# ledCubeV2_0.net
KiCad netlist of a schematic drawn in EAGLE
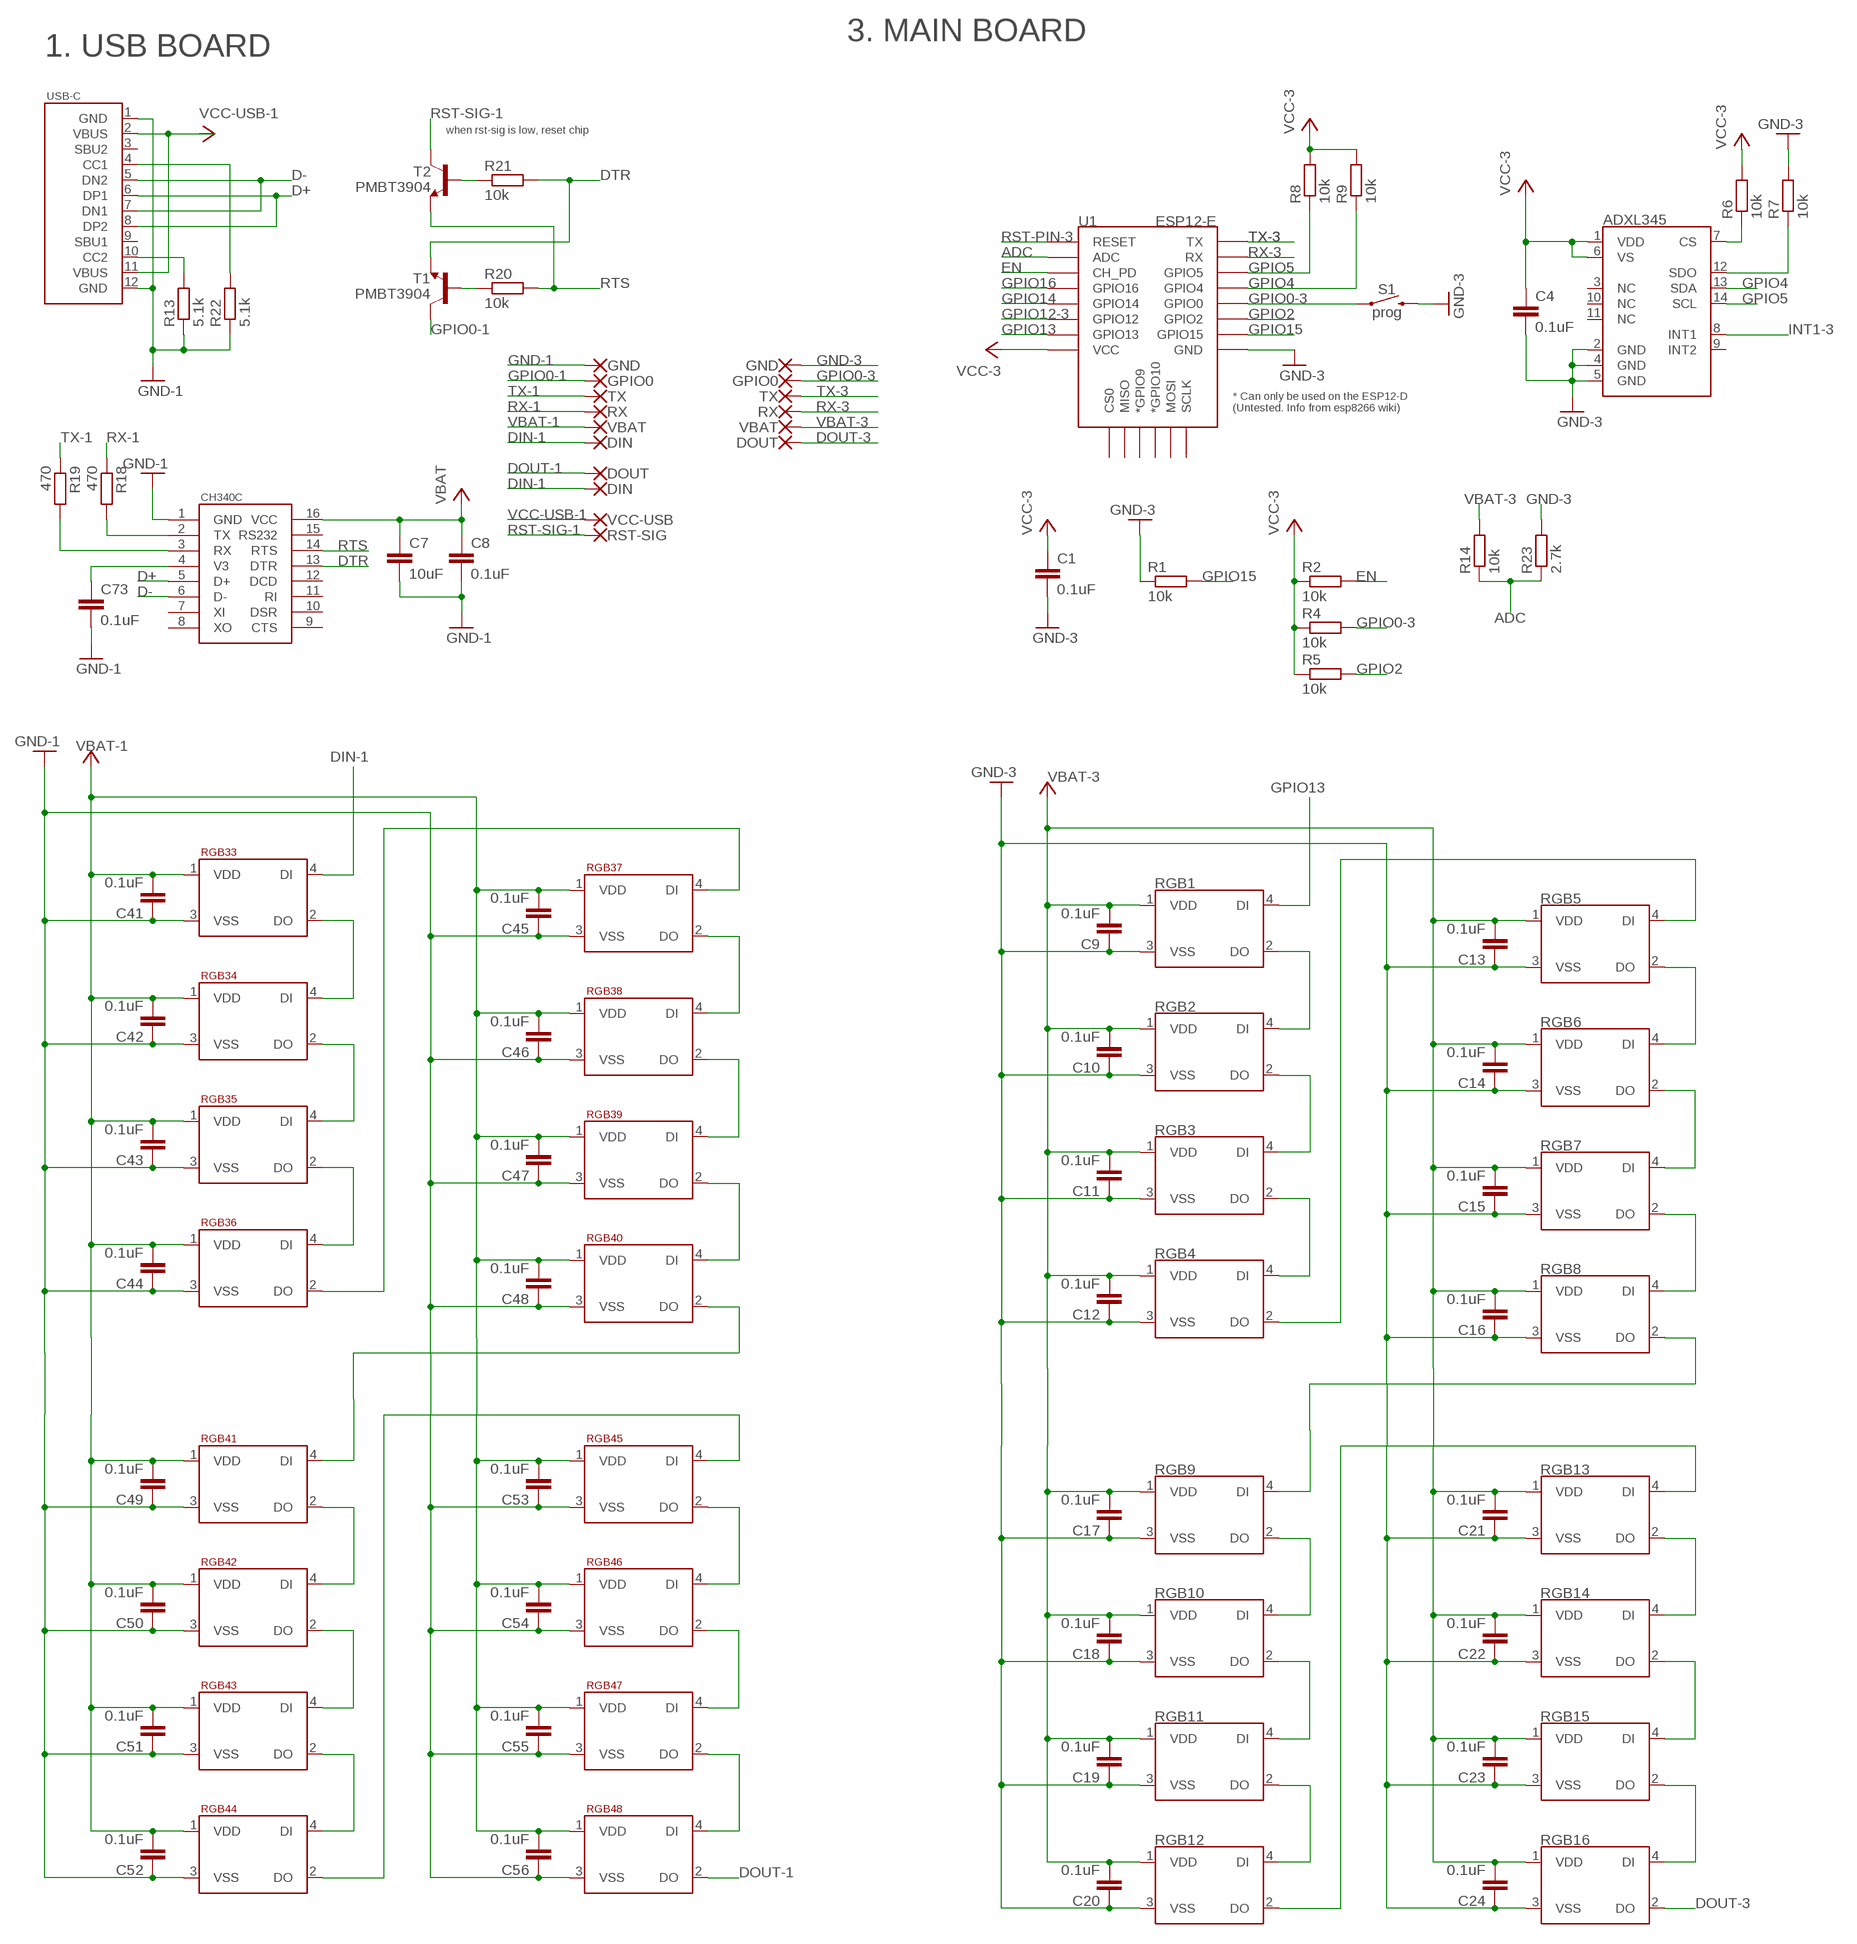
[diagram p0: schematic, sheet 1, part 1 of 2]
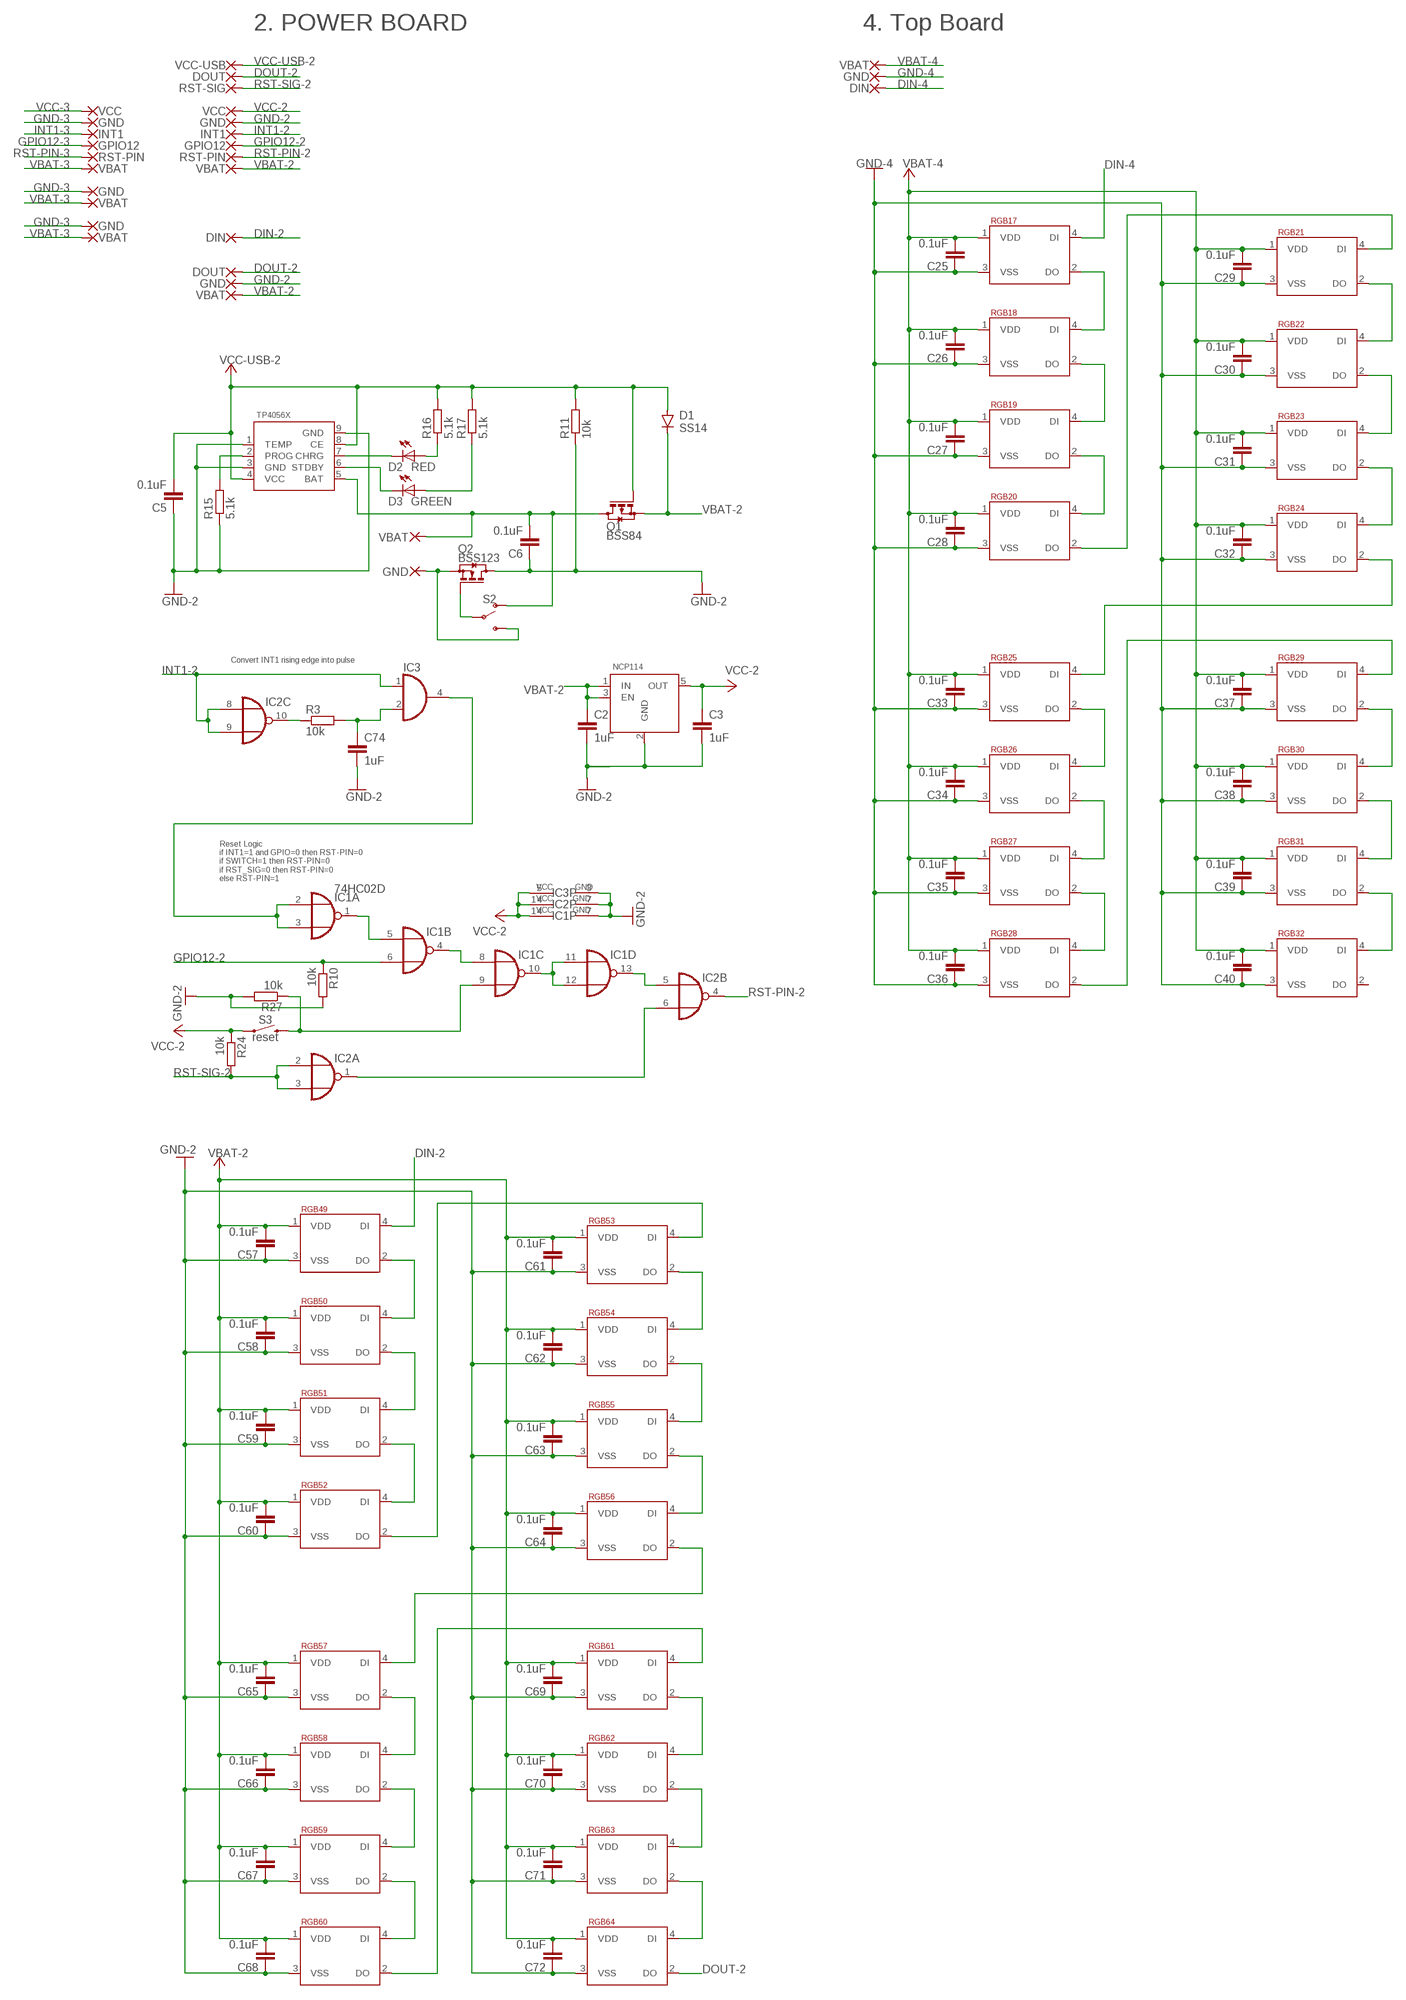
[diagram p1: schematic, sheet 1, part 2 of 2]

(export (version "E")
  (design (tool "Eeschema 10.0.6"))
  (components
    (comp (ref "ADXL345")
      (value "ADXL345")
      (footprint "eagle-import:LGA-14")
      (libsource (lib "eagle-import") (part "ADXL345"))
    )
    (comp (ref "C1")
      (value "0.1uF")
      (footprint "eagle-import:C0603")
      (libsource (lib "eagle-import") (part "CC0603"))
    )
    (comp (ref "C2")
      (value "1uF")
      (footprint "eagle-import:C0603")
      (libsource (lib "eagle-import") (part "CC0603"))
    )
    (comp (ref "C3")
      (value "1uF")
      (footprint "eagle-import:C0603")
      (libsource (lib "eagle-import") (part "CC0603"))
    )
    (comp (ref "C4")
      (value "0.1uF")
      (footprint "eagle-import:C0603")
      (libsource (lib "eagle-import") (part "CC0603"))
    )
    (comp (ref "C5")
      (value "0.1uF")
      (footprint "eagle-import:C0603")
      (libsource (lib "eagle-import") (part "CC0603"))
    )
    (comp (ref "C6")
      (value "0.1uF")
      (footprint "eagle-import:C0603")
      (libsource (lib "eagle-import") (part "CC0603"))
    )
    (comp (ref "C7")
      (value "10uF")
      (footprint "eagle-import:C0603")
      (libsource (lib "eagle-import") (part "CC0603"))
    )
    (comp (ref "C8")
      (value "0.1uF")
      (footprint "eagle-import:C0603")
      (libsource (lib "eagle-import") (part "CC0603"))
    )
    (comp (ref "C9")
      (value "0.1uF")
      (footprint "eagle-import:C0603")
      (libsource (lib "eagle-import") (part "CC0603"))
    )
    (comp (ref "C10")
      (value "0.1uF")
      (footprint "eagle-import:C0603")
      (libsource (lib "eagle-import") (part "CC0603"))
    )
    (comp (ref "C11")
      (value "0.1uF")
      (footprint "eagle-import:C0603")
      (libsource (lib "eagle-import") (part "CC0603"))
    )
    (comp (ref "C12")
      (value "0.1uF")
      (footprint "eagle-import:C0603")
      (libsource (lib "eagle-import") (part "CC0603"))
    )
    (comp (ref "C13")
      (value "0.1uF")
      (footprint "eagle-import:C0603")
      (libsource (lib "eagle-import") (part "CC0603"))
    )
    (comp (ref "C14")
      (value "0.1uF")
      (footprint "eagle-import:C0603")
      (libsource (lib "eagle-import") (part "CC0603"))
    )
    (comp (ref "C15")
      (value "0.1uF")
      (footprint "eagle-import:C0603")
      (libsource (lib "eagle-import") (part "CC0603"))
    )
    (comp (ref "C16")
      (value "0.1uF")
      (footprint "eagle-import:C0603")
      (libsource (lib "eagle-import") (part "CC0603"))
    )
    (comp (ref "C17")
      (value "0.1uF")
      (footprint "eagle-import:C0603")
      (libsource (lib "eagle-import") (part "CC0603"))
    )
    (comp (ref "C18")
      (value "0.1uF")
      (footprint "eagle-import:C0603")
      (libsource (lib "eagle-import") (part "CC0603"))
    )
    (comp (ref "C19")
      (value "0.1uF")
      (footprint "eagle-import:C0603")
      (libsource (lib "eagle-import") (part "CC0603"))
    )
    (comp (ref "C20")
      (value "0.1uF")
      (footprint "eagle-import:C0603")
      (libsource (lib "eagle-import") (part "CC0603"))
    )
    (comp (ref "C21")
      (value "0.1uF")
      (footprint "eagle-import:C0603")
      (libsource (lib "eagle-import") (part "CC0603"))
    )
    (comp (ref "C22")
      (value "0.1uF")
      (footprint "eagle-import:C0603")
      (libsource (lib "eagle-import") (part "CC0603"))
    )
    (comp (ref "C23")
      (value "0.1uF")
      (footprint "eagle-import:C0603")
      (libsource (lib "eagle-import") (part "CC0603"))
    )
    (comp (ref "C24")
      (value "0.1uF")
      (footprint "eagle-import:C0603")
      (libsource (lib "eagle-import") (part "CC0603"))
    )
    (comp (ref "C25")
      (value "0.1uF")
      (footprint "eagle-import:C0603")
      (libsource (lib "eagle-import") (part "CC0603"))
    )
    (comp (ref "C26")
      (value "0.1uF")
      (footprint "eagle-import:C0603")
      (libsource (lib "eagle-import") (part "CC0603"))
    )
    (comp (ref "C27")
      (value "0.1uF")
      (footprint "eagle-import:C0603")
      (libsource (lib "eagle-import") (part "CC0603"))
    )
    (comp (ref "C28")
      (value "0.1uF")
      (footprint "eagle-import:C0603")
      (libsource (lib "eagle-import") (part "CC0603"))
    )
    (comp (ref "C29")
      (value "0.1uF")
      (footprint "eagle-import:C0603")
      (libsource (lib "eagle-import") (part "CC0603"))
    )
    (comp (ref "C30")
      (value "0.1uF")
      (footprint "eagle-import:C0603")
      (libsource (lib "eagle-import") (part "CC0603"))
    )
    (comp (ref "C31")
      (value "0.1uF")
      (footprint "eagle-import:C0603")
      (libsource (lib "eagle-import") (part "CC0603"))
    )
    (comp (ref "C32")
      (value "0.1uF")
      (footprint "eagle-import:C0603")
      (libsource (lib "eagle-import") (part "CC0603"))
    )
    (comp (ref "C33")
      (value "0.1uF")
      (footprint "eagle-import:C0603")
      (libsource (lib "eagle-import") (part "CC0603"))
    )
    (comp (ref "C34")
      (value "0.1uF")
      (footprint "eagle-import:C0603")
      (libsource (lib "eagle-import") (part "CC0603"))
    )
    (comp (ref "C35")
      (value "0.1uF")
      (footprint "eagle-import:C0603")
      (libsource (lib "eagle-import") (part "CC0603"))
    )
    (comp (ref "C36")
      (value "0.1uF")
      (footprint "eagle-import:C0603")
      (libsource (lib "eagle-import") (part "CC0603"))
    )
    (comp (ref "C37")
      (value "0.1uF")
      (footprint "eagle-import:C0603")
      (libsource (lib "eagle-import") (part "CC0603"))
    )
    (comp (ref "C38")
      (value "0.1uF")
      (footprint "eagle-import:C0603")
      (libsource (lib "eagle-import") (part "CC0603"))
    )
    (comp (ref "C39")
      (value "0.1uF")
      (footprint "eagle-import:C0603")
      (libsource (lib "eagle-import") (part "CC0603"))
    )
    (comp (ref "C40")
      (value "0.1uF")
      (footprint "eagle-import:C0603")
      (libsource (lib "eagle-import") (part "CC0603"))
    )
    (comp (ref "C41")
      (value "0.1uF")
      (footprint "eagle-import:C0603")
      (libsource (lib "eagle-import") (part "CC0603"))
    )
    (comp (ref "C42")
      (value "0.1uF")
      (footprint "eagle-import:C0603")
      (libsource (lib "eagle-import") (part "CC0603"))
    )
    (comp (ref "C43")
      (value "0.1uF")
      (footprint "eagle-import:C0603")
      (libsource (lib "eagle-import") (part "CC0603"))
    )
    (comp (ref "C44")
      (value "0.1uF")
      (footprint "eagle-import:C0603")
      (libsource (lib "eagle-import") (part "CC0603"))
    )
    (comp (ref "C45")
      (value "0.1uF")
      (footprint "eagle-import:C0603")
      (libsource (lib "eagle-import") (part "CC0603"))
    )
    (comp (ref "C46")
      (value "0.1uF")
      (footprint "eagle-import:C0603")
      (libsource (lib "eagle-import") (part "CC0603"))
    )
    (comp (ref "C47")
      (value "0.1uF")
      (footprint "eagle-import:C0603")
      (libsource (lib "eagle-import") (part "CC0603"))
    )
    (comp (ref "C48")
      (value "0.1uF")
      (footprint "eagle-import:C0603")
      (libsource (lib "eagle-import") (part "CC0603"))
    )
    (comp (ref "C49")
      (value "0.1uF")
      (footprint "eagle-import:C0603")
      (libsource (lib "eagle-import") (part "CC0603"))
    )
    (comp (ref "C50")
      (value "0.1uF")
      (footprint "eagle-import:C0603")
      (libsource (lib "eagle-import") (part "CC0603"))
    )
    (comp (ref "C51")
      (value "0.1uF")
      (footprint "eagle-import:C0603")
      (libsource (lib "eagle-import") (part "CC0603"))
    )
    (comp (ref "C52")
      (value "0.1uF")
      (footprint "eagle-import:C0603")
      (libsource (lib "eagle-import") (part "CC0603"))
    )
    (comp (ref "C53")
      (value "0.1uF")
      (footprint "eagle-import:C0603")
      (libsource (lib "eagle-import") (part "CC0603"))
    )
    (comp (ref "C54")
      (value "0.1uF")
      (footprint "eagle-import:C0603")
      (libsource (lib "eagle-import") (part "CC0603"))
    )
    (comp (ref "C55")
      (value "0.1uF")
      (footprint "eagle-import:C0603")
      (libsource (lib "eagle-import") (part "CC0603"))
    )
    (comp (ref "C56")
      (value "0.1uF")
      (footprint "eagle-import:C0603")
      (libsource (lib "eagle-import") (part "CC0603"))
    )
    (comp (ref "C57")
      (value "0.1uF")
      (footprint "eagle-import:C0603")
      (libsource (lib "eagle-import") (part "CC0603"))
    )
    (comp (ref "C58")
      (value "0.1uF")
      (footprint "eagle-import:C0603")
      (libsource (lib "eagle-import") (part "CC0603"))
    )
    (comp (ref "C59")
      (value "0.1uF")
      (footprint "eagle-import:C0603")
      (libsource (lib "eagle-import") (part "CC0603"))
    )
    (comp (ref "C60")
      (value "0.1uF")
      (footprint "eagle-import:C0603")
      (libsource (lib "eagle-import") (part "CC0603"))
    )
    (comp (ref "C61")
      (value "0.1uF")
      (footprint "eagle-import:C0603")
      (libsource (lib "eagle-import") (part "CC0603"))
    )
    (comp (ref "C62")
      (value "0.1uF")
      (footprint "eagle-import:C0603")
      (libsource (lib "eagle-import") (part "CC0603"))
    )
    (comp (ref "C63")
      (value "0.1uF")
      (footprint "eagle-import:C0603")
      (libsource (lib "eagle-import") (part "CC0603"))
    )
    (comp (ref "C64")
      (value "0.1uF")
      (footprint "eagle-import:C0603")
      (libsource (lib "eagle-import") (part "CC0603"))
    )
    (comp (ref "C65")
      (value "0.1uF")
      (footprint "eagle-import:C0603")
      (libsource (lib "eagle-import") (part "CC0603"))
    )
    (comp (ref "C66")
      (value "0.1uF")
      (footprint "eagle-import:C0603")
      (libsource (lib "eagle-import") (part "CC0603"))
    )
    (comp (ref "C67")
      (value "0.1uF")
      (footprint "eagle-import:C0603")
      (libsource (lib "eagle-import") (part "CC0603"))
    )
    (comp (ref "C68")
      (value "0.1uF")
      (footprint "eagle-import:C0603")
      (libsource (lib "eagle-import") (part "CC0603"))
    )
    (comp (ref "C69")
      (value "0.1uF")
      (footprint "eagle-import:C0603")
      (libsource (lib "eagle-import") (part "CC0603"))
    )
    (comp (ref "C70")
      (value "0.1uF")
      (footprint "eagle-import:C0603")
      (libsource (lib "eagle-import") (part "CC0603"))
    )
    (comp (ref "C71")
      (value "0.1uF")
      (footprint "eagle-import:C0603")
      (libsource (lib "eagle-import") (part "CC0603"))
    )
    (comp (ref "C72")
      (value "0.1uF")
      (footprint "eagle-import:C0603")
      (libsource (lib "eagle-import") (part "CC0603"))
    )
    (comp (ref "C73")
      (value "0.1uF")
      (footprint "eagle-import:C0603")
      (libsource (lib "eagle-import") (part "CC0603"))
    )
    (comp (ref "C74")
      (value "1uF")
      (footprint "eagle-import:C0603")
      (libsource (lib "eagle-import") (part "CC0603"))
    )
    (comp (ref "CH340C")
      (value "CH340G")
      (footprint "eagle-import:SOIC16")
      (libsource (lib "eagle-import") (part "CH340G"))
    )
    (comp (ref "D1")
      (value "SS14")
      (footprint "eagle-import:DO-214AC")
      (libsource (lib "eagle-import") (part "DIODE-DO-214AC"))
    )
    (comp (ref "D2")
      (value "RED")
      (footprint "eagle-import:LED_SML0603")
      (libsource (lib "eagle-import") (part "LED_ESML0603"))
    )
    (comp (ref "D3")
      (value "GREEN")
      (footprint "eagle-import:LED_SML0603")
      (libsource (lib "eagle-import") (part "LED_ESML0603"))
    )
    (comp (ref "GND")
      (value "SMD2")
      (footprint "eagle-import:SMD1,27-2,54")
      (libsource (lib "eagle-import") (part "SMD2"))
    )
    (comp (ref "GND-1")
      (value "GND")
      (footprint "eagle-import:SMD1,27-2,54")
      (libsource (lib "eagle-import") (part "SMD2"))
    )
    (comp (ref "GND-2")
      (value "RX")
      (footprint "eagle-import:SMD1,27-2,54")
      (libsource (lib "eagle-import") (part "SMD2"))
    )
    (comp (ref "GPIO0-1")
      (value "GPIO0")
      (footprint "eagle-import:SMD1,27-2,54")
      (libsource (lib "eagle-import") (part "SMD2"))
    )
    (comp (ref "GPIO0-2")
      (value "GPIO0")
      (footprint "eagle-import:SMD1,27-2,54")
      (libsource (lib "eagle-import") (part "SMD2"))
    )
    (comp (ref "IC1")
      (value "74HC02D")
      (footprint "eagle-import:SO14")
      (libsource (lib "eagle-import") (part "7402DHC"))
    )
    (comp (ref "IC2")
      (value "74HC02D")
      (footprint "eagle-import:SO14")
      (libsource (lib "eagle-import") (part "7402DHC"))
    )
    (comp (ref "IC3")
      (value "74AHC1G08DCK")
      (footprint "eagle-import:SC70-5")
      (libsource (lib "eagle-import") (part "741G08DCKAHC"))
    )
    (comp (ref "NCP114")
      (value "NCP114")
      (footprint "eagle-import:TSOP-5")
      (libsource (lib "eagle-import") (part "NCP114"))
    )
    (comp (ref "Q1")
      (value "BSS84")
      (footprint "eagle-import:SOT23")
      (libsource (lib "eagle-import") (part "BSS84"))
    )
    (comp (ref "Q2")
      (value "BSS123")
      (footprint "eagle-import:SOT23")
      (libsource (lib "eagle-import") (part "BSS123"))
    )
    (comp (ref "R1")
      (value "10k")
      (footprint "eagle-import:R0603")
      (libsource (lib "eagle-import") (part "RR0603"))
    )
    (comp (ref "R2")
      (value "10k")
      (footprint "eagle-import:R0603")
      (libsource (lib "eagle-import") (part "RR0603"))
    )
    (comp (ref "R3")
      (value "10k")
      (footprint "eagle-import:R0603")
      (libsource (lib "eagle-import") (part "RR0603"))
    )
    (comp (ref "R4")
      (value "10k")
      (footprint "eagle-import:R0603")
      (libsource (lib "eagle-import") (part "RR0603"))
    )
    (comp (ref "R5")
      (value "10k")
      (footprint "eagle-import:R0603")
      (libsource (lib "eagle-import") (part "RR0603"))
    )
    (comp (ref "R6")
      (value "10k")
      (footprint "eagle-import:R0603")
      (libsource (lib "eagle-import") (part "RR0603"))
    )
    (comp (ref "R7")
      (value "10k")
      (footprint "eagle-import:R0603")
      (libsource (lib "eagle-import") (part "RR0603"))
    )
    (comp (ref "R8")
      (value "10k")
      (footprint "eagle-import:R0603")
      (libsource (lib "eagle-import") (part "RR0603"))
    )
    (comp (ref "R9")
      (value "10k")
      (footprint "eagle-import:R0603")
      (libsource (lib "eagle-import") (part "RR0603"))
    )
    (comp (ref "R10")
      (value "10k")
      (footprint "eagle-import:R0603")
      (libsource (lib "eagle-import") (part "RR0603"))
    )
    (comp (ref "R11")
      (value "10k")
      (footprint "eagle-import:R0603")
      (libsource (lib "eagle-import") (part "RR0603"))
    )
    (comp (ref "R13")
      (value "5.1k")
      (footprint "eagle-import:R0603")
      (libsource (lib "eagle-import") (part "RR0603"))
    )
    (comp (ref "R14")
      (value "10k")
      (footprint "eagle-import:R0603")
      (libsource (lib "eagle-import") (part "RR0603"))
    )
    (comp (ref "R15")
      (value "5.1k")
      (footprint "eagle-import:R0603")
      (libsource (lib "eagle-import") (part "RR0603"))
    )
    (comp (ref "R16")
      (value "5.1k")
      (footprint "eagle-import:R0603")
      (libsource (lib "eagle-import") (part "RR0603"))
    )
    (comp (ref "R17")
      (value "5.1k")
      (footprint "eagle-import:R0603")
      (libsource (lib "eagle-import") (part "RR0603"))
    )
    (comp (ref "R18")
      (value "470")
      (footprint "eagle-import:R0603")
      (libsource (lib "eagle-import") (part "RR0603"))
    )
    (comp (ref "R19")
      (value "470")
      (footprint "eagle-import:R0603")
      (libsource (lib "eagle-import") (part "RR0603"))
    )
    (comp (ref "R20")
      (value "10k")
      (footprint "eagle-import:R0603")
      (libsource (lib "eagle-import") (part "RR0603"))
    )
    (comp (ref "R21")
      (value "10k")
      (footprint "eagle-import:R0603")
      (libsource (lib "eagle-import") (part "RR0603"))
    )
    (comp (ref "R22")
      (value "5.1k")
      (footprint "eagle-import:R0603")
      (libsource (lib "eagle-import") (part "RR0603"))
    )
    (comp (ref "R23")
      (value "2.7k")
      (footprint "eagle-import:R0603")
      (libsource (lib "eagle-import") (part "RR0603"))
    )
    (comp (ref "R24")
      (value "10k")
      (footprint "eagle-import:R0603")
      (libsource (lib "eagle-import") (part "RR0603"))
    )
    (comp (ref "R27")
      (value "10k")
      (footprint "eagle-import:R0603")
      (libsource (lib "eagle-import") (part "RR0603"))
    )
    (comp (ref "RGB1")
      (value "WS2812B")
      (footprint "eagle-import:WS2812B-MINI")
      (libsource (lib "eagle-import") (part "WS2812B-MINI"))
    )
    (comp (ref "RGB2")
      (value "WS2812B")
      (footprint "eagle-import:WS2812B-MINI")
      (libsource (lib "eagle-import") (part "WS2812B-MINI"))
    )
    (comp (ref "RGB3")
      (value "WS2812B")
      (footprint "eagle-import:WS2812B-MINI")
      (libsource (lib "eagle-import") (part "WS2812B-MINI"))
    )
    (comp (ref "RGB4")
      (value "WS2812B")
      (footprint "eagle-import:WS2812B-MINI")
      (libsource (lib "eagle-import") (part "WS2812B-MINI"))
    )
    (comp (ref "RGB5")
      (value "WS2812B")
      (footprint "eagle-import:WS2812B-MINI")
      (libsource (lib "eagle-import") (part "WS2812B-MINI"))
    )
    (comp (ref "RGB6")
      (value "WS2812B")
      (footprint "eagle-import:WS2812B-MINI")
      (libsource (lib "eagle-import") (part "WS2812B-MINI"))
    )
    (comp (ref "RGB7")
      (value "WS2812B")
      (footprint "eagle-import:WS2812B-MINI")
      (libsource (lib "eagle-import") (part "WS2812B-MINI"))
    )
    (comp (ref "RGB8")
      (value "WS2812B")
      (footprint "eagle-import:WS2812B-MINI")
      (libsource (lib "eagle-import") (part "WS2812B-MINI"))
    )
    (comp (ref "RGB9")
      (value "WS2812B")
      (footprint "eagle-import:WS2812B-MINI")
      (libsource (lib "eagle-import") (part "WS2812B-MINI"))
    )
    (comp (ref "RGB10")
      (value "WS2812B")
      (footprint "eagle-import:WS2812B-MINI")
      (libsource (lib "eagle-import") (part "WS2812B-MINI"))
    )
    (comp (ref "RGB11")
      (value "WS2812B")
      (footprint "eagle-import:WS2812B-MINI")
      (libsource (lib "eagle-import") (part "WS2812B-MINI"))
    )
    (comp (ref "RGB12")
      (value "WS2812B")
      (footprint "eagle-import:WS2812B-MINI")
      (libsource (lib "eagle-import") (part "WS2812B-MINI"))
    )
    (comp (ref "RGB13")
      (value "WS2812B")
      (footprint "eagle-import:WS2812B-MINI")
      (libsource (lib "eagle-import") (part "WS2812B-MINI"))
    )
    (comp (ref "RGB14")
      (value "WS2812B")
      (footprint "eagle-import:WS2812B-MINI")
      (libsource (lib "eagle-import") (part "WS2812B-MINI"))
    )
    (comp (ref "RGB15")
      (value "WS2812B")
      (footprint "eagle-import:WS2812B-MINI")
      (libsource (lib "eagle-import") (part "WS2812B-MINI"))
    )
    (comp (ref "RGB16")
      (value "WS2812B")
      (footprint "eagle-import:WS2812B-MINI")
      (libsource (lib "eagle-import") (part "WS2812B-MINI"))
    )
    (comp (ref "RGB17")
      (value "WS2812B")
      (footprint "eagle-import:WS2812B-MINI")
      (libsource (lib "eagle-import") (part "WS2812B-MINI"))
    )
    (comp (ref "RGB18")
      (value "WS2812B")
      (footprint "eagle-import:WS2812B-MINI")
      (libsource (lib "eagle-import") (part "WS2812B-MINI"))
    )
    (comp (ref "RGB19")
      (value "WS2812B")
      (footprint "eagle-import:WS2812B-MINI")
      (libsource (lib "eagle-import") (part "WS2812B-MINI"))
    )
    (comp (ref "RGB20")
      (value "WS2812B")
      (footprint "eagle-import:WS2812B-MINI")
      (libsource (lib "eagle-import") (part "WS2812B-MINI"))
    )
    (comp (ref "RGB21")
      (value "WS2812B")
      (footprint "eagle-import:WS2812B-MINI")
      (libsource (lib "eagle-import") (part "WS2812B-MINI"))
    )
    (comp (ref "RGB22")
      (value "WS2812B")
      (footprint "eagle-import:WS2812B-MINI")
      (libsource (lib "eagle-import") (part "WS2812B-MINI"))
    )
    (comp (ref "RGB23")
      (value "WS2812B")
      (footprint "eagle-import:WS2812B-MINI")
      (libsource (lib "eagle-import") (part "WS2812B-MINI"))
    )
    (comp (ref "RGB24")
      (value "WS2812B")
      (footprint "eagle-import:WS2812B-MINI")
      (libsource (lib "eagle-import") (part "WS2812B-MINI"))
    )
    (comp (ref "RGB25")
      (value "WS2812B")
      (footprint "eagle-import:WS2812B-MINI")
      (libsource (lib "eagle-import") (part "WS2812B-MINI"))
    )
    (comp (ref "RGB26")
      (value "WS2812B")
      (footprint "eagle-import:WS2812B-MINI")
      (libsource (lib "eagle-import") (part "WS2812B-MINI"))
    )
    (comp (ref "RGB27")
      (value "WS2812B")
      (footprint "eagle-import:WS2812B-MINI")
      (libsource (lib "eagle-import") (part "WS2812B-MINI"))
    )
    (comp (ref "RGB28")
      (value "WS2812B")
      (footprint "eagle-import:WS2812B-MINI")
      (libsource (lib "eagle-import") (part "WS2812B-MINI"))
    )
    (comp (ref "RGB29")
      (value "WS2812B")
      (footprint "eagle-import:WS2812B-MINI")
      (libsource (lib "eagle-import") (part "WS2812B-MINI"))
    )
    (comp (ref "RGB30")
      (value "WS2812B")
      (footprint "eagle-import:WS2812B-MINI")
      (libsource (lib "eagle-import") (part "WS2812B-MINI"))
    )
    (comp (ref "RGB31")
      (value "WS2812B")
      (footprint "eagle-import:WS2812B-MINI")
      (libsource (lib "eagle-import") (part "WS2812B-MINI"))
    )
    (comp (ref "RGB32")
      (value "WS2812B")
      (footprint "eagle-import:WS2812B-MINI")
      (libsource (lib "eagle-import") (part "WS2812B-MINI"))
    )
    (comp (ref "RGB33")
      (value "WS2812B")
      (footprint "eagle-import:WS2812B-MINI")
      (libsource (lib "eagle-import") (part "WS2812B-MINI"))
    )
    (comp (ref "RGB34")
      (value "WS2812B")
      (footprint "eagle-import:WS2812B-MINI")
      (libsource (lib "eagle-import") (part "WS2812B-MINI"))
    )
    (comp (ref "RGB35")
      (value "WS2812B")
      (footprint "eagle-import:WS2812B-MINI")
      (libsource (lib "eagle-import") (part "WS2812B-MINI"))
    )
    (comp (ref "RGB36")
      (value "WS2812B")
      (footprint "eagle-import:WS2812B-MINI")
      (libsource (lib "eagle-import") (part "WS2812B-MINI"))
    )
    (comp (ref "RGB37")
      (value "WS2812B")
      (footprint "eagle-import:WS2812B-MINI")
      (libsource (lib "eagle-import") (part "WS2812B-MINI"))
    )
    (comp (ref "RGB38")
      (value "WS2812B")
      (footprint "eagle-import:WS2812B-MINI")
      (libsource (lib "eagle-import") (part "WS2812B-MINI"))
    )
    (comp (ref "RGB39")
      (value "WS2812B")
      (footprint "eagle-import:WS2812B-MINI")
      (libsource (lib "eagle-import") (part "WS2812B-MINI"))
    )
    (comp (ref "RGB40")
      (value "WS2812B")
      (footprint "eagle-import:WS2812B-MINI")
      (libsource (lib "eagle-import") (part "WS2812B-MINI"))
    )
    (comp (ref "RGB41")
      (value "WS2812B")
      (footprint "eagle-import:WS2812B-MINI")
      (libsource (lib "eagle-import") (part "WS2812B-MINI"))
    )
    (comp (ref "RGB42")
      (value "WS2812B")
      (footprint "eagle-import:WS2812B-MINI")
      (libsource (lib "eagle-import") (part "WS2812B-MINI"))
    )
    (comp (ref "RGB43")
      (value "WS2812B")
      (footprint "eagle-import:WS2812B-MINI")
      (libsource (lib "eagle-import") (part "WS2812B-MINI"))
    )
    (comp (ref "RGB44")
      (value "WS2812B")
      (footprint "eagle-import:WS2812B-MINI")
      (libsource (lib "eagle-import") (part "WS2812B-MINI"))
    )
    (comp (ref "RGB45")
      (value "WS2812B")
      (footprint "eagle-import:WS2812B-MINI")
      (libsource (lib "eagle-import") (part "WS2812B-MINI"))
    )
    (comp (ref "RGB46")
      (value "WS2812B")
      (footprint "eagle-import:WS2812B-MINI")
      (libsource (lib "eagle-import") (part "WS2812B-MINI"))
    )
    (comp (ref "RGB47")
      (value "WS2812B")
      (footprint "eagle-import:WS2812B-MINI")
      (libsource (lib "eagle-import") (part "WS2812B-MINI"))
    )
    (comp (ref "RGB48")
      (value "WS2812B")
      (footprint "eagle-import:WS2812B-MINI")
      (libsource (lib "eagle-import") (part "WS2812B-MINI"))
    )
    (comp (ref "RGB49")
      (value "WS2812B")
      (footprint "eagle-import:WS2812B-MINI")
      (libsource (lib "eagle-import") (part "WS2812B-MINI"))
    )
    (comp (ref "RGB50")
      (value "WS2812B")
      (footprint "eagle-import:WS2812B-MINI")
      (libsource (lib "eagle-import") (part "WS2812B-MINI"))
    )
    (comp (ref "RGB51")
      (value "WS2812B")
      (footprint "eagle-import:WS2812B-MINI")
      (libsource (lib "eagle-import") (part "WS2812B-MINI"))
    )
    (comp (ref "RGB52")
      (value "WS2812B")
      (footprint "eagle-import:WS2812B-MINI")
      (libsource (lib "eagle-import") (part "WS2812B-MINI"))
    )
    (comp (ref "RGB53")
      (value "WS2812B")
      (footprint "eagle-import:WS2812B-MINI")
      (libsource (lib "eagle-import") (part "WS2812B-MINI"))
    )
    (comp (ref "RGB54")
      (value "WS2812B")
      (footprint "eagle-import:WS2812B-MINI")
      (libsource (lib "eagle-import") (part "WS2812B-MINI"))
    )
    (comp (ref "RGB55")
      (value "WS2812B")
      (footprint "eagle-import:WS2812B-MINI")
      (libsource (lib "eagle-import") (part "WS2812B-MINI"))
    )
    (comp (ref "RGB56")
      (value "WS2812B")
      (footprint "eagle-import:WS2812B-MINI")
      (libsource (lib "eagle-import") (part "WS2812B-MINI"))
    )
    (comp (ref "RGB57")
      (value "WS2812B")
      (footprint "eagle-import:WS2812B-MINI")
      (libsource (lib "eagle-import") (part "WS2812B-MINI"))
    )
    (comp (ref "RGB58")
      (value "WS2812B")
      (footprint "eagle-import:WS2812B-MINI")
      (libsource (lib "eagle-import") (part "WS2812B-MINI"))
    )
    (comp (ref "RGB59")
      (value "WS2812B")
      (footprint "eagle-import:WS2812B-MINI")
      (libsource (lib "eagle-import") (part "WS2812B-MINI"))
    )
    (comp (ref "RGB60")
      (value "WS2812B")
      (footprint "eagle-import:WS2812B-MINI")
      (libsource (lib "eagle-import") (part "WS2812B-MINI"))
    )
    (comp (ref "RGB61")
      (value "WS2812B")
      (footprint "eagle-import:WS2812B-MINI")
      (libsource (lib "eagle-import") (part "WS2812B-MINI"))
    )
    (comp (ref "RGB62")
      (value "WS2812B")
      (footprint "eagle-import:WS2812B-MINI")
      (libsource (lib "eagle-import") (part "WS2812B-MINI"))
    )
    (comp (ref "RGB63")
      (value "WS2812B")
      (footprint "eagle-import:WS2812B-MINI")
      (libsource (lib "eagle-import") (part "WS2812B-MINI"))
    )
    (comp (ref "RGB64")
      (value "WS2812B")
      (footprint "eagle-import:WS2812B-MINI")
      (libsource (lib "eagle-import") (part "WS2812B-MINI"))
    )
    (comp (ref "RST-SIG-1")
      (value "RST-SIG")
      (footprint "eagle-import:SMD1,27-2,54")
      (libsource (lib "eagle-import") (part "SMD2"))
    )
    (comp (ref "RST-SIG-2")
      (value "TX")
      (footprint "eagle-import:SMD1,27-2,54")
      (libsource (lib "eagle-import") (part "SMD2"))
    )
    (comp (ref "RX-1")
      (value "RX")
      (footprint "eagle-import:SMD1,27-2,54")
      (libsource (lib "eagle-import") (part "SMD2"))
    )
    (comp (ref "RX-2")
      (value "GND")
      (footprint "eagle-import:SMD1,27-2,54")
      (libsource (lib "eagle-import") (part "SMD2"))
    )
    (comp (ref "RX-3")
      (value "GND")
      (footprint "eagle-import:SMD1,27-2,54")
      (libsource (lib "eagle-import") (part "SMD2"))
    )
    (comp (ref "S1")
      (value "prog")
      (footprint "eagle-import:TACTILE_SWITCH_SMD_6.0X3.5MM")
      (libsource (lib "eagle-import") (part "MOMENTARY-SWITCH-SPST-SMD-6.0X3.5MM"))
    )
    (comp (ref "S2")
      (value "ON/CHRG")
      (footprint "eagle-import:SWITCH_SPST_SMD_A")
      (libsource (lib "eagle-import") (part "SWITCH-SPDT-SMD-RIGHT-ANGLE"))
    )
    (comp (ref "S3")
      (value "reset")
      (footprint "eagle-import:TACTILE_SWITCH_SMD_6.0X3.5MM")
      (libsource (lib "eagle-import") (part "MOMENTARY-SWITCH-SPST-SMD-6.0X3.5MM"))
    )
    (comp (ref "T1")
      (value "PMBT3904")
      (footprint "eagle-import:SOT23-BEC")
      (libsource (lib "eagle-import") (part "-NPN-SOT23-BECMMBT3904LT1"))
    )
    (comp (ref "T2")
      (value "PMBT3904")
      (footprint "eagle-import:SOT23-BEC")
      (libsource (lib "eagle-import") (part "-NPN-SOT23-BECMMBT3904LT1"))
    )
    (comp (ref "TP4056X")
      (value "TP4056X")
      (footprint "eagle-import:ESPO8")
      (libsource (lib "eagle-import") (part "TP4056X"))
    )
    (comp (ref "TX-1")
      (value "TX")
      (footprint "eagle-import:SMD1,27-2,54")
      (libsource (lib "eagle-import") (part "SMD2"))
    )
    (comp (ref "TX-3")
      (value "DIN")
      (footprint "eagle-import:SMD1,27-2,54")
      (libsource (lib "eagle-import") (part "SMD2"))
    )
    (comp (ref "U1")
      (value "ESP12-E")
      (footprint "eagle-import:ESP12E-SMD")
      (libsource (lib "eagle-import") (part "ESP12ESMD"))
    )
    (comp (ref "USB-C")
      (value "USB-C")
      (footprint "eagle-import:USB-C")
      (libsource (lib "eagle-import") (part "USB-C"))
    )
    (comp (ref "VBAT")
      (value "SMD2")
      (footprint "eagle-import:SMD1,27-2,54")
      (libsource (lib "eagle-import") (part "SMD2"))
    )
    (comp (ref "VCC-USB-1")
      (value "VBAT")
      (footprint "eagle-import:SMD1,27-2,54")
      (libsource (lib "eagle-import") (part "SMD2"))
    )
    (comp (ref "VCC-USB-3")
      (value "VBAT")
      (footprint "eagle-import:SMD1,27-2,54")
      (libsource (lib "eagle-import") (part "SMD2"))
    )
    (comp (ref "VCC-USB-4")
      (value "DIN")
      (footprint "eagle-import:SMD1,27-2,54")
      (libsource (lib "eagle-import") (part "SMD2"))
    )
    (comp (ref "VCC-USB-5")
      (value "DOUT")
      (footprint "eagle-import:SMD1,27-2,54")
      (libsource (lib "eagle-import") (part "SMD2"))
    )
    (comp (ref "VCC-USB-6")
      (value "DOUT")
      (footprint "eagle-import:SMD1,27-2,54")
      (libsource (lib "eagle-import") (part "SMD2"))
    )
    (comp (ref "VCC-USB-7")
      (value "DIN")
      (footprint "eagle-import:SMD1,27-2,54")
      (libsource (lib "eagle-import") (part "SMD2"))
    )
    (comp (ref "VCC-USB-8")
      (value "DOUT")
      (footprint "eagle-import:SMD1,27-2,54")
      (libsource (lib "eagle-import") (part "SMD2"))
    )
    (comp (ref "VCC-USB-9")
      (value "DIN")
      (footprint "eagle-import:SMD1,27-2,54")
      (libsource (lib "eagle-import") (part "SMD2"))
    )
    (comp (ref "VCC-USB-10")
      (value "GND")
      (footprint "eagle-import:SMD1,27-2,54")
      (libsource (lib "eagle-import") (part "SMD2"))
    )
    (comp (ref "VCC-USB-11")
      (value "VCC")
      (footprint "eagle-import:SMD1,27-2,54")
      (libsource (lib "eagle-import") (part "SMD2"))
    )
    (comp (ref "VCC-USB-12")
      (value "INT1")
      (footprint "eagle-import:SMD1,27-2,54")
      (libsource (lib "eagle-import") (part "SMD2"))
    )
    (comp (ref "VCC-USB-13")
      (value "GND")
      (footprint "eagle-import:SMD1,27-2,54")
      (libsource (lib "eagle-import") (part "SMD2"))
    )
    (comp (ref "VCC-USB-14")
      (value "VCC-USB")
      (footprint "eagle-import:SMD1,27-2,54")
      (libsource (lib "eagle-import") (part "SMD2"))
    )
    (comp (ref "VCC-USB-15")
      (value "DOUT")
      (footprint "eagle-import:SMD1,27-2,54")
      (libsource (lib "eagle-import") (part "SMD2"))
    )
    (comp (ref "VCC-USB-16")
      (value "RST-SIG")
      (footprint "eagle-import:SMD1,27-2,54")
      (libsource (lib "eagle-import") (part "SMD2"))
    )
    (comp (ref "VCC-USB-17")
      (value "GPIO12")
      (footprint "eagle-import:SMD1,27-2,54")
      (libsource (lib "eagle-import") (part "SMD2"))
    )
    (comp (ref "VCC-USB-18")
      (value "RST-PIN")
      (footprint "eagle-import:SMD1,27-2,54")
      (libsource (lib "eagle-import") (part "SMD2"))
    )
    (comp (ref "VCC-USB-19")
      (value "GND")
      (footprint "eagle-import:SMD1,27-2,54")
      (libsource (lib "eagle-import") (part "SMD2"))
    )
    (comp (ref "VCC-USB-20")
      (value "VCC-USB")
      (footprint "eagle-import:SMD1,27-2,54")
      (libsource (lib "eagle-import") (part "SMD2"))
    )
    (comp (ref "VCC-USB-21")
      (value "VCC")
      (footprint "eagle-import:SMD1,27-2,54")
      (libsource (lib "eagle-import") (part "SMD2"))
    )
    (comp (ref "VCC-USB-22")
      (value "INT1")
      (footprint "eagle-import:SMD1,27-2,54")
      (libsource (lib "eagle-import") (part "SMD2"))
    )
    (comp (ref "VCC-USB-23")
      (value "GPIO12")
      (footprint "eagle-import:SMD1,27-2,54")
      (libsource (lib "eagle-import") (part "SMD2"))
    )
    (comp (ref "VCC-USB-24")
      (value "RST-PIN")
      (footprint "eagle-import:SMD1,27-2,54")
      (libsource (lib "eagle-import") (part "SMD2"))
    )
    (comp (ref "VCC-USB-25")
      (value "GND")
      (footprint "eagle-import:SMD1,27-2,54")
      (libsource (lib "eagle-import") (part "SMD2"))
    )
    (comp (ref "VCC-USB-26")
      (value "GND")
      (footprint "eagle-import:SMD1,27-2,54")
      (libsource (lib "eagle-import") (part "SMD2"))
    )
    (comp (ref "VCC1")
      (value "VBAT")
      (footprint "eagle-import:SMD1,27-2,54")
      (libsource (lib "eagle-import") (part "SMD2"))
    )
    (comp (ref "VCC2")
      (value "VBAT")
      (footprint "eagle-import:SMD1,27-2,54")
      (libsource (lib "eagle-import") (part "SMD2"))
    )
    (comp (ref "VCC3")
      (value "VBAT")
      (footprint "eagle-import:SMD1,27-2,54")
      (libsource (lib "eagle-import") (part "SMD2"))
    )
    (comp (ref "VCC4")
      (value "VBAT")
      (footprint "eagle-import:SMD1,27-2,54")
      (libsource (lib "eagle-import") (part "SMD2"))
    )
    (comp (ref "VCC5")
      (value "VBAT")
      (footprint "eagle-import:SMD1,27-2,54")
      (libsource (lib "eagle-import") (part "SMD2"))
    )
    (comp (ref "VCC6")
      (value "VBAT")
      (footprint "eagle-import:SMD1,27-2,54")
      (libsource (lib "eagle-import") (part "SMD2"))
    )
  )
  (nets
    (net (code "1") (name "/ADC") (class "Default")
      (node (ref "R14") (pin "1") (pinfunction "1_1") (pintype "passive"))
      (node (ref "R23") (pin "1") (pinfunction "1_1") (pintype "passive"))
      (node (ref "U1") (pin "ADC") (pinfunction "ADC_ADC") (pintype "bidirectional"))
    )
    (net (code "2") (name "/D+") (class "Default")
      (node (ref "CH340C") (pin "5") (pinfunction "D+_5") (pintype "bidirectional"))
      (node (ref "USB-C") (pin "6") (pinfunction "DP1_6") (pintype "bidirectional"))
      (node (ref "USB-C") (pin "8") (pinfunction "DP2_8") (pintype "bidirectional"))
    )
    (net (code "3") (name "/D-") (class "Default")
      (node (ref "CH340C") (pin "6") (pinfunction "D-_6") (pintype "bidirectional"))
      (node (ref "USB-C") (pin "5") (pinfunction "DN2_5") (pintype "bidirectional"))
      (node (ref "USB-C") (pin "7") (pinfunction "DN1_7") (pintype "bidirectional"))
    )
    (net (code "4") (name "/DIN-1") (class "Default")
      (node (ref "RGB33") (pin "4") (pinfunction "DI_4") (pintype "bidirectional"))
      (node (ref "VCC-USB-4") (pin "1") (pinfunction "P_1") (pintype "passive"))
      (node (ref "VCC-USB-7") (pin "1") (pinfunction "P_1") (pintype "passive"))
    )
    (net (code "5") (name "/DIN-2") (class "Default")
      (node (ref "RGB49") (pin "4") (pinfunction "DI_4") (pintype "bidirectional"))
      (node (ref "VCC-USB-9") (pin "1") (pinfunction "P_1") (pintype "passive"))
    )
    (net (code "6") (name "/DIN-4") (class "Default")
      (node (ref "RGB17") (pin "4") (pinfunction "DI_4") (pintype "bidirectional"))
      (node (ref "TX-3") (pin "1") (pinfunction "P_1") (pintype "passive"))
    )
    (net (code "7") (name "/DOUT-1") (class "Default")
      (node (ref "RGB48") (pin "2") (pinfunction "DO_2") (pintype "bidirectional"))
      (node (ref "VCC-USB-6") (pin "1") (pinfunction "P_1") (pintype "passive"))
    )
    (net (code "8") (name "/DOUT-2") (class "Default")
      (node (ref "RGB64") (pin "2") (pinfunction "DO_2") (pintype "bidirectional"))
      (node (ref "VCC-USB-15") (pin "1") (pinfunction "P_1") (pintype "passive"))
      (node (ref "VCC-USB-8") (pin "1") (pinfunction "P_1") (pintype "passive"))
    )
    (net (code "9") (name "/DOUT-3") (class "Default")
      (node (ref "RGB16") (pin "2") (pinfunction "DO_2") (pintype "bidirectional"))
      (node (ref "VCC-USB-5") (pin "1") (pinfunction "P_1") (pintype "passive"))
    )
    (net (code "10") (name "/DTR") (class "Default")
      (node (ref "CH340C") (pin "13") (pinfunction "DTR_13") (pintype "bidirectional"))
      (node (ref "R21") (pin "2") (pinfunction "2_2") (pintype "passive"))
      (node (ref "T1") (pin "E") (pinfunction "E_E") (pintype "passive"))
    )
    (net (code "11") (name "/EN") (class "Default")
      (node (ref "R2") (pin "2") (pinfunction "2_2") (pintype "passive"))
      (node (ref "U1") (pin "CH_PD") (pinfunction "CH_PD_CH_PD") (pintype "bidirectional"))
    )
    (net (code "12") (name "/GPIO0-1") (class "Default")
      (node (ref "GPIO0-1") (pin "1") (pinfunction "P_1") (pintype "passive"))
      (node (ref "T1") (pin "C") (pinfunction "C_C") (pintype "passive"))
    )
    (net (code "13") (name "/GPIO0-3") (class "Default")
      (node (ref "GPIO0-2") (pin "1") (pinfunction "P_1") (pintype "passive"))
      (node (ref "R4") (pin "2") (pinfunction "2_2") (pintype "passive"))
      (node (ref "S1") (pin "1") (pinfunction "1_1") (pintype "passive"))
      (node (ref "U1") (pin "GPIO0") (pinfunction "GPIO0_GPIO0") (pintype "bidirectional"))
    )
    (net (code "14") (name "/GPIO2") (class "Default")
      (node (ref "R5") (pin "2") (pinfunction "2_2") (pintype "passive"))
      (node (ref "U1") (pin "GPIO2") (pinfunction "GPIO2_GPIO2") (pintype "bidirectional"))
    )
    (net (code "15") (name "/GPIO4") (class "Default")
      (node (ref "ADXL345") (pin "13") (pinfunction "SDA_13") (pintype "bidirectional"))
      (node (ref "R9") (pin "1") (pinfunction "1_1") (pintype "passive"))
      (node (ref "U1") (pin "GPIO4") (pinfunction "GPIO4_GPIO4") (pintype "bidirectional"))
    )
    (net (code "16") (name "/GPIO5") (class "Default")
      (node (ref "ADXL345") (pin "14") (pinfunction "SCL_14") (pintype "bidirectional"))
      (node (ref "R8") (pin "1") (pinfunction "1_1") (pintype "passive"))
      (node (ref "U1") (pin "GPIO5") (pinfunction "GPIO5_GPIO5") (pintype "bidirectional"))
    )
    (net (code "17") (name "/GPIO12-2") (class "Default")
      (node (ref "IC1") (pin "6") (pinfunction "I1_6") (pintype "input"))
      (node (ref "R10") (pin "1") (pinfunction "1_1") (pintype "passive"))
      (node (ref "VCC-USB-17") (pin "1") (pinfunction "P_1") (pintype "passive"))
    )
    (net (code "18") (name "/GPIO12-3") (class "Default")
      (node (ref "U1") (pin "GPIO12") (pinfunction "GPIO12_GPIO12") (pintype "bidirectional"))
      (node (ref "VCC-USB-23") (pin "1") (pinfunction "P_1") (pintype "passive"))
    )
    (net (code "19") (name "/GPIO13") (class "Default")
      (node (ref "RGB1") (pin "4") (pinfunction "DI_4") (pintype "bidirectional"))
      (node (ref "U1") (pin "GPIO13") (pinfunction "GPIO13_GPIO13") (pintype "bidirectional"))
    )
    (net (code "20") (name "/GPIO14") (class "Default")
      (node (ref "U1") (pin "GPIO14") (pinfunction "GPIO14_GPIO14") (pintype "bidirectional"))
    )
    (net (code "21") (name "/GPIO15") (class "Default")
      (node (ref "R1") (pin "2") (pinfunction "2_2") (pintype "passive"))
      (node (ref "U1") (pin "GPIO15") (pinfunction "GPIO15_GPIO15") (pintype "bidirectional"))
    )
    (net (code "22") (name "/GPIO16") (class "Default")
      (node (ref "U1") (pin "GPIO16") (pinfunction "GPIO16_GPIO16") (pintype "bidirectional"))
    )
    (net (code "23") (name "/INT1-2") (class "Default")
      (node (ref "IC2") (pin "8") (pinfunction "I0_8") (pintype "input"))
      (node (ref "IC2") (pin "9") (pinfunction "I1_9") (pintype "input"))
      (node (ref "IC3") (pin "1") (pinfunction "I0_1") (pintype "input"))
      (node (ref "VCC-USB-12") (pin "1") (pinfunction "P_1") (pintype "passive"))
    )
    (net (code "24") (name "/INT1-3") (class "Default")
      (node (ref "ADXL345") (pin "8") (pinfunction "INT1_8") (pintype "bidirectional"))
      (node (ref "VCC-USB-22") (pin "1") (pinfunction "P_1") (pintype "passive"))
    )
    (net (code "25") (name "/RST-PIN-2") (class "Default")
      (node (ref "IC2") (pin "4") (pinfunction "O_4") (pintype "output"))
      (node (ref "VCC-USB-18") (pin "1") (pinfunction "P_1") (pintype "passive"))
    )
    (net (code "26") (name "/RST-PIN-3") (class "Default")
      (node (ref "U1") (pin "RESET") (pinfunction "RESET_RESET") (pintype "bidirectional"))
      (node (ref "VCC-USB-24") (pin "1") (pinfunction "P_1") (pintype "passive"))
    )
    (net (code "27") (name "/RST-SIG-1") (class "Default")
      (node (ref "RST-SIG-1") (pin "1") (pinfunction "P_1") (pintype "passive"))
      (node (ref "T2") (pin "C") (pinfunction "C_C") (pintype "passive"))
    )
    (net (code "28") (name "/RST-SIG-2") (class "Default")
      (node (ref "IC2") (pin "2") (pinfunction "I0_2") (pintype "input"))
      (node (ref "IC2") (pin "3") (pinfunction "I1_3") (pintype "input"))
      (node (ref "R24") (pin "2") (pinfunction "2_2") (pintype "passive"))
      (node (ref "VCC-USB-16") (pin "1") (pinfunction "P_1") (pintype "passive"))
    )
    (net (code "29") (name "/RTS") (class "Default")
      (node (ref "CH340C") (pin "14") (pinfunction "RTS_14") (pintype "bidirectional"))
      (node (ref "R20") (pin "2") (pinfunction "2_2") (pintype "passive"))
      (node (ref "T2") (pin "E") (pinfunction "E_E") (pintype "passive"))
    )
    (net (code "30") (name "/RX-1") (class "Default")
      (node (ref "R18") (pin "1") (pinfunction "1_1") (pintype "passive"))
      (node (ref "RX-1") (pin "1") (pinfunction "P_1") (pintype "passive"))
    )
    (net (code "31") (name "/RX-3") (class "Default")
      (node (ref "GND-2") (pin "1") (pinfunction "P_1") (pintype "passive"))
      (node (ref "U1") (pin "RXD0") (pinfunction "RX_RXD0") (pintype "bidirectional"))
    )
    (net (code "32") (name "/TX-1") (class "Default")
      (node (ref "R19") (pin "1") (pinfunction "1_1") (pintype "passive"))
      (node (ref "TX-1") (pin "1") (pinfunction "P_1") (pintype "passive"))
    )
    (net (code "33") (name "/TX-3") (class "Default")
      (node (ref "RST-SIG-2") (pin "1") (pinfunction "P_1") (pintype "passive"))
      (node (ref "U1") (pin "TXD0") (pinfunction "TX_TXD0") (pintype "bidirectional"))
    )
    (net (code "34") (name "GND-1") (class "Default")
      (node (ref "C41") (pin "1") (pinfunction "1_1") (pintype "passive"))
      (node (ref "C42") (pin "1") (pinfunction "1_1") (pintype "passive"))
      (node (ref "C43") (pin "1") (pinfunction "1_1") (pintype "passive"))
      (node (ref "C44") (pin "1") (pinfunction "1_1") (pintype "passive"))
      (node (ref "C45") (pin "1") (pinfunction "1_1") (pintype "passive"))
      (node (ref "C46") (pin "1") (pinfunction "1_1") (pintype "passive"))
      (node (ref "C47") (pin "1") (pinfunction "1_1") (pintype "passive"))
      (node (ref "C48") (pin "1") (pinfunction "1_1") (pintype "passive"))
      (node (ref "C49") (pin "1") (pinfunction "1_1") (pintype "passive"))
      (node (ref "C50") (pin "1") (pinfunction "1_1") (pintype "passive"))
      (node (ref "C51") (pin "1") (pinfunction "1_1") (pintype "passive"))
      (node (ref "C52") (pin "1") (pinfunction "1_1") (pintype "passive"))
      (node (ref "C53") (pin "1") (pinfunction "1_1") (pintype "passive"))
      (node (ref "C54") (pin "1") (pinfunction "1_1") (pintype "passive"))
      (node (ref "C55") (pin "1") (pinfunction "1_1") (pintype "passive"))
      (node (ref "C56") (pin "1") (pinfunction "1_1") (pintype "passive"))
      (node (ref "C7") (pin "2") (pinfunction "2_2") (pintype "passive"))
      (node (ref "C73") (pin "2") (pinfunction "2_2") (pintype "passive"))
      (node (ref "C8") (pin "2") (pinfunction "2_2") (pintype "passive"))
      (node (ref "CH340C") (pin "1") (pinfunction "GND_1") (pintype "bidirectional"))
      (node (ref "GND-1") (pin "1") (pinfunction "P_1") (pintype "passive"))
      (node (ref "R13") (pin "1") (pinfunction "1_1") (pintype "passive"))
      (node (ref "R22") (pin "1") (pinfunction "1_1") (pintype "passive"))
      (node (ref "RGB33") (pin "3") (pinfunction "VSS_3") (pintype "bidirectional"))
      (node (ref "RGB34") (pin "3") (pinfunction "VSS_3") (pintype "bidirectional"))
      (node (ref "RGB35") (pin "3") (pinfunction "VSS_3") (pintype "bidirectional"))
      (node (ref "RGB36") (pin "3") (pinfunction "VSS_3") (pintype "bidirectional"))
      (node (ref "RGB37") (pin "3") (pinfunction "VSS_3") (pintype "bidirectional"))
      (node (ref "RGB38") (pin "3") (pinfunction "VSS_3") (pintype "bidirectional"))
      (node (ref "RGB39") (pin "3") (pinfunction "VSS_3") (pintype "bidirectional"))
      (node (ref "RGB40") (pin "3") (pinfunction "VSS_3") (pintype "bidirectional"))
      (node (ref "RGB41") (pin "3") (pinfunction "VSS_3") (pintype "bidirectional"))
      (node (ref "RGB42") (pin "3") (pinfunction "VSS_3") (pintype "bidirectional"))
      (node (ref "RGB43") (pin "3") (pinfunction "VSS_3") (pintype "bidirectional"))
      (node (ref "RGB44") (pin "3") (pinfunction "VSS_3") (pintype "bidirectional"))
      (node (ref "RGB45") (pin "3") (pinfunction "VSS_3") (pintype "bidirectional"))
      (node (ref "RGB46") (pin "3") (pinfunction "VSS_3") (pintype "bidirectional"))
      (node (ref "RGB47") (pin "3") (pinfunction "VSS_3") (pintype "bidirectional"))
      (node (ref "RGB48") (pin "3") (pinfunction "VSS_3") (pintype "bidirectional"))
      (node (ref "USB-C") (pin "1") (pinfunction "GND_1") (pintype "bidirectional"))
      (node (ref "USB-C") (pin "12") (pinfunction "GND_12") (pintype "bidirectional"))
    )
    (net (code "35") (name "GND-2") (class "Default")
      (node (ref "C2") (pin "2") (pinfunction "2_2") (pintype "passive"))
      (node (ref "C3") (pin "2") (pinfunction "2_2") (pintype "passive"))
      (node (ref "C5") (pin "1") (pinfunction "1_1") (pintype "passive"))
      (node (ref "C57") (pin "1") (pinfunction "1_1") (pintype "passive"))
      (node (ref "C58") (pin "1") (pinfunction "1_1") (pintype "passive"))
      (node (ref "C59") (pin "1") (pinfunction "1_1") (pintype "passive"))
      (node (ref "C6") (pin "1") (pinfunction "1_1") (pintype "passive"))
      (node (ref "C60") (pin "1") (pinfunction "1_1") (pintype "passive"))
      (node (ref "C61") (pin "1") (pinfunction "1_1") (pintype "passive"))
      (node (ref "C62") (pin "1") (pinfunction "1_1") (pintype "passive"))
      (node (ref "C63") (pin "1") (pinfunction "1_1") (pintype "passive"))
      (node (ref "C64") (pin "1") (pinfunction "1_1") (pintype "passive"))
      (node (ref "C65") (pin "1") (pinfunction "1_1") (pintype "passive"))
      (node (ref "C66") (pin "1") (pinfunction "1_1") (pintype "passive"))
      (node (ref "C67") (pin "1") (pinfunction "1_1") (pintype "passive"))
      (node (ref "C68") (pin "1") (pinfunction "1_1") (pintype "passive"))
      (node (ref "C69") (pin "1") (pinfunction "1_1") (pintype "passive"))
      (node (ref "C70") (pin "1") (pinfunction "1_1") (pintype "passive"))
      (node (ref "C71") (pin "1") (pinfunction "1_1") (pintype "passive"))
      (node (ref "C72") (pin "1") (pinfunction "1_1") (pintype "passive"))
      (node (ref "C74") (pin "2") (pinfunction "2_2") (pintype "passive"))
      (node (ref "IC1") (pin "7") (pinfunction "GND_7") (pintype "power_in"))
      (node (ref "IC2") (pin "7") (pinfunction "GND_7") (pintype "power_in"))
      (node (ref "IC3") (pin "3") (pinfunction "GND_3") (pintype "power_in"))
      (node (ref "NCP114") (pin "2") (pinfunction "GND_2") (pintype "bidirectional"))
      (node (ref "Q2") (pin "3") (pinfunction "D_3") (pintype "passive"))
      (node (ref "R10") (pin "2") (pinfunction "2_2") (pintype "passive"))
      (node (ref "R11") (pin "1") (pinfunction "1_1") (pintype "passive"))
      (node (ref "R15") (pin "1") (pinfunction "1_1") (pintype "passive"))
      (node (ref "R27") (pin "2") (pinfunction "2_2") (pintype "passive"))
      (node (ref "RGB49") (pin "3") (pinfunction "VSS_3") (pintype "bidirectional"))
      (node (ref "RGB50") (pin "3") (pinfunction "VSS_3") (pintype "bidirectional"))
      (node (ref "RGB51") (pin "3") (pinfunction "VSS_3") (pintype "bidirectional"))
      (node (ref "RGB52") (pin "3") (pinfunction "VSS_3") (pintype "bidirectional"))
      (node (ref "RGB53") (pin "3") (pinfunction "VSS_3") (pintype "bidirectional"))
      (node (ref "RGB54") (pin "3") (pinfunction "VSS_3") (pintype "bidirectional"))
      (node (ref "RGB55") (pin "3") (pinfunction "VSS_3") (pintype "bidirectional"))
      (node (ref "RGB56") (pin "3") (pinfunction "VSS_3") (pintype "bidirectional"))
      (node (ref "RGB57") (pin "3") (pinfunction "VSS_3") (pintype "bidirectional"))
      (node (ref "RGB58") (pin "3") (pinfunction "VSS_3") (pintype "bidirectional"))
      (node (ref "RGB59") (pin "3") (pinfunction "VSS_3") (pintype "bidirectional"))
      (node (ref "RGB60") (pin "3") (pinfunction "VSS_3") (pintype "bidirectional"))
      (node (ref "RGB61") (pin "3") (pinfunction "VSS_3") (pintype "bidirectional"))
      (node (ref "RGB62") (pin "3") (pinfunction "VSS_3") (pintype "bidirectional"))
      (node (ref "RGB63") (pin "3") (pinfunction "VSS_3") (pintype "bidirectional"))
      (node (ref "RGB64") (pin "3") (pinfunction "VSS_3") (pintype "bidirectional"))
      (node (ref "TP4056X") (pin "1") (pinfunction "TEMP_1") (pintype "bidirectional"))
      (node (ref "TP4056X") (pin "3") (pinfunction "GND_3") (pintype "bidirectional"))
      (node (ref "TP4056X") (pin "9") (pinfunction "GND_9") (pintype "bidirectional"))
      (node (ref "VCC-USB-10") (pin "1") (pinfunction "P_1") (pintype "passive"))
      (node (ref "VCC-USB-19") (pin "1") (pinfunction "P_1") (pintype "passive"))
    )
    (net (code "36") (name "GND-3") (class "Default")
      (node (ref "ADXL345") (pin "2") (pinfunction "GND_2") (pintype "bidirectional"))
      (node (ref "ADXL345") (pin "4") (pinfunction "GND_4") (pintype "bidirectional"))
      (node (ref "ADXL345") (pin "5") (pinfunction "GND_5") (pintype "bidirectional"))
      (node (ref "C1") (pin "2") (pinfunction "2_2") (pintype "passive"))
      (node (ref "C10") (pin "1") (pinfunction "1_1") (pintype "passive"))
      (node (ref "C11") (pin "1") (pinfunction "1_1") (pintype "passive"))
      (node (ref "C12") (pin "1") (pinfunction "1_1") (pintype "passive"))
      (node (ref "C13") (pin "1") (pinfunction "1_1") (pintype "passive"))
      (node (ref "C14") (pin "1") (pinfunction "1_1") (pintype "passive"))
      (node (ref "C15") (pin "1") (pinfunction "1_1") (pintype "passive"))
      (node (ref "C16") (pin "1") (pinfunction "1_1") (pintype "passive"))
      (node (ref "C17") (pin "1") (pinfunction "1_1") (pintype "passive"))
      (node (ref "C18") (pin "1") (pinfunction "1_1") (pintype "passive"))
      (node (ref "C19") (pin "1") (pinfunction "1_1") (pintype "passive"))
      (node (ref "C20") (pin "1") (pinfunction "1_1") (pintype "passive"))
      (node (ref "C21") (pin "1") (pinfunction "1_1") (pintype "passive"))
      (node (ref "C22") (pin "1") (pinfunction "1_1") (pintype "passive"))
      (node (ref "C23") (pin "1") (pinfunction "1_1") (pintype "passive"))
      (node (ref "C24") (pin "1") (pinfunction "1_1") (pintype "passive"))
      (node (ref "C4") (pin "2") (pinfunction "2_2") (pintype "passive"))
      (node (ref "C9") (pin "1") (pinfunction "1_1") (pintype "passive"))
      (node (ref "R1") (pin "1") (pinfunction "1_1") (pintype "passive"))
      (node (ref "R23") (pin "2") (pinfunction "2_2") (pintype "passive"))
      (node (ref "R7") (pin "2") (pinfunction "2_2") (pintype "passive"))
      (node (ref "RGB1") (pin "3") (pinfunction "VSS_3") (pintype "bidirectional"))
      (node (ref "RGB10") (pin "3") (pinfunction "VSS_3") (pintype "bidirectional"))
      (node (ref "RGB11") (pin "3") (pinfunction "VSS_3") (pintype "bidirectional"))
      (node (ref "RGB12") (pin "3") (pinfunction "VSS_3") (pintype "bidirectional"))
      (node (ref "RGB13") (pin "3") (pinfunction "VSS_3") (pintype "bidirectional"))
      (node (ref "RGB14") (pin "3") (pinfunction "VSS_3") (pintype "bidirectional"))
      (node (ref "RGB15") (pin "3") (pinfunction "VSS_3") (pintype "bidirectional"))
      (node (ref "RGB16") (pin "3") (pinfunction "VSS_3") (pintype "bidirectional"))
      (node (ref "RGB2") (pin "3") (pinfunction "VSS_3") (pintype "bidirectional"))
      (node (ref "RGB3") (pin "3") (pinfunction "VSS_3") (pintype "bidirectional"))
      (node (ref "RGB4") (pin "3") (pinfunction "VSS_3") (pintype "bidirectional"))
      (node (ref "RGB5") (pin "3") (pinfunction "VSS_3") (pintype "bidirectional"))
      (node (ref "RGB6") (pin "3") (pinfunction "VSS_3") (pintype "bidirectional"))
      (node (ref "RGB7") (pin "3") (pinfunction "VSS_3") (pintype "bidirectional"))
      (node (ref "RGB8") (pin "3") (pinfunction "VSS_3") (pintype "bidirectional"))
      (node (ref "RGB9") (pin "3") (pinfunction "VSS_3") (pintype "bidirectional"))
      (node (ref "RX-2") (pin "1") (pinfunction "P_1") (pintype "passive"))
      (node (ref "S1") (pin "2") (pinfunction "2_2") (pintype "passive"))
      (node (ref "U1") (pin "GND") (pinfunction "GND_GND") (pintype "bidirectional"))
      (node (ref "VCC-USB-13") (pin "1") (pinfunction "P_1") (pintype "passive"))
      (node (ref "VCC-USB-25") (pin "1") (pinfunction "P_1") (pintype "passive"))
      (node (ref "VCC-USB-26") (pin "1") (pinfunction "P_1") (pintype "passive"))
    )
    (net (code "37") (name "GND-4") (class "Default")
      (node (ref "C25") (pin "1") (pinfunction "1_1") (pintype "passive"))
      (node (ref "C26") (pin "1") (pinfunction "1_1") (pintype "passive"))
      (node (ref "C27") (pin "1") (pinfunction "1_1") (pintype "passive"))
      (node (ref "C28") (pin "1") (pinfunction "1_1") (pintype "passive"))
      (node (ref "C29") (pin "1") (pinfunction "1_1") (pintype "passive"))
      (node (ref "C30") (pin "1") (pinfunction "1_1") (pintype "passive"))
      (node (ref "C31") (pin "1") (pinfunction "1_1") (pintype "passive"))
      (node (ref "C32") (pin "1") (pinfunction "1_1") (pintype "passive"))
      (node (ref "C33") (pin "1") (pinfunction "1_1") (pintype "passive"))
      (node (ref "C34") (pin "1") (pinfunction "1_1") (pintype "passive"))
      (node (ref "C35") (pin "1") (pinfunction "1_1") (pintype "passive"))
      (node (ref "C36") (pin "1") (pinfunction "1_1") (pintype "passive"))
      (node (ref "C37") (pin "1") (pinfunction "1_1") (pintype "passive"))
      (node (ref "C38") (pin "1") (pinfunction "1_1") (pintype "passive"))
      (node (ref "C39") (pin "1") (pinfunction "1_1") (pintype "passive"))
      (node (ref "C40") (pin "1") (pinfunction "1_1") (pintype "passive"))
      (node (ref "RGB17") (pin "3") (pinfunction "VSS_3") (pintype "bidirectional"))
      (node (ref "RGB18") (pin "3") (pinfunction "VSS_3") (pintype "bidirectional"))
      (node (ref "RGB19") (pin "3") (pinfunction "VSS_3") (pintype "bidirectional"))
      (node (ref "RGB20") (pin "3") (pinfunction "VSS_3") (pintype "bidirectional"))
      (node (ref "RGB21") (pin "3") (pinfunction "VSS_3") (pintype "bidirectional"))
      (node (ref "RGB22") (pin "3") (pinfunction "VSS_3") (pintype "bidirectional"))
      (node (ref "RGB23") (pin "3") (pinfunction "VSS_3") (pintype "bidirectional"))
      (node (ref "RGB24") (pin "3") (pinfunction "VSS_3") (pintype "bidirectional"))
      (node (ref "RGB25") (pin "3") (pinfunction "VSS_3") (pintype "bidirectional"))
      (node (ref "RGB26") (pin "3") (pinfunction "VSS_3") (pintype "bidirectional"))
      (node (ref "RGB27") (pin "3") (pinfunction "VSS_3") (pintype "bidirectional"))
      (node (ref "RGB28") (pin "3") (pinfunction "VSS_3") (pintype "bidirectional"))
      (node (ref "RGB29") (pin "3") (pinfunction "VSS_3") (pintype "bidirectional"))
      (node (ref "RGB30") (pin "3") (pinfunction "VSS_3") (pintype "bidirectional"))
      (node (ref "RGB31") (pin "3") (pinfunction "VSS_3") (pintype "bidirectional"))
      (node (ref "RGB32") (pin "3") (pinfunction "VSS_3") (pintype "bidirectional"))
      (node (ref "RX-3") (pin "1") (pinfunction "P_1") (pintype "passive"))
    )
    (net (code "38") (name "Net-(ADXL345-CS)") (class "Default")
      (node (ref "ADXL345") (pin "7") (pinfunction "CS_7") (pintype "bidirectional"))
      (node (ref "R6") (pin "1") (pinfunction "1_1") (pintype "passive"))
    )
    (net (code "39") (name "Net-(ADXL345-SDO)") (class "Default")
      (node (ref "ADXL345") (pin "12") (pinfunction "SDO_12") (pintype "bidirectional"))
      (node (ref "R7") (pin "1") (pinfunction "1_1") (pintype "passive"))
    )
    (net (code "40") (name "Net-(CH340C-RX)") (class "Default")
      (node (ref "CH340C") (pin "3") (pinfunction "RX_3") (pintype "bidirectional"))
      (node (ref "R19") (pin "2") (pinfunction "2_2") (pintype "passive"))
    )
    (net (code "41") (name "Net-(CH340C-TX)") (class "Default")
      (node (ref "CH340C") (pin "2") (pinfunction "TX_2") (pintype "bidirectional"))
      (node (ref "R18") (pin "2") (pinfunction "2_2") (pintype "passive"))
    )
    (net (code "42") (name "Net-(CH340C-V3)") (class "Default")
      (node (ref "C73") (pin "1") (pinfunction "1_1") (pintype "passive"))
      (node (ref "CH340C") (pin "4") (pinfunction "V3_4") (pintype "bidirectional"))
    )
    (net (code "43") (name "Net-(D2-PadA)") (class "Default")
      (node (ref "D2") (pin "A") (pinfunction "A_A") (pintype "passive"))
      (node (ref "R16") (pin "1") (pinfunction "1_1") (pintype "passive"))
    )
    (net (code "44") (name "Net-(D3-PadA)") (class "Default")
      (node (ref "D3") (pin "A") (pinfunction "A_A") (pintype "passive"))
      (node (ref "R17") (pin "1") (pinfunction "1_1") (pintype "passive"))
    )
    (net (code "45") (name "Net-(GND-P)") (class "Default")
      (node (ref "GND") (pin "1") (pinfunction "P_1") (pintype "passive"))
      (node (ref "Q2") (pin "2") (pinfunction "S_2") (pintype "passive"))
      (node (ref "S2") (pin "3") (pinfunction "S_3") (pintype "passive"))
    )
    (net (code "46") (name "Net-(IC1A-I0)") (class "Default")
      (node (ref "IC1") (pin "2") (pinfunction "I0_2") (pintype "input"))
      (node (ref "IC1") (pin "3") (pinfunction "I1_3") (pintype "input"))
      (node (ref "IC3") (pin "4") (pinfunction "O_4") (pintype "output"))
    )
    (net (code "47") (name "Net-(IC1A-O)") (class "Default")
      (node (ref "IC1") (pin "1") (pinfunction "O_1") (pintype "output"))
      (node (ref "IC1") (pin "5") (pinfunction "I0_5") (pintype "input"))
    )
    (net (code "48") (name "Net-(IC1B-O)") (class "Default")
      (node (ref "IC1") (pin "4") (pinfunction "O_4") (pintype "output"))
      (node (ref "IC1") (pin "8") (pinfunction "I0_8") (pintype "input"))
    )
    (net (code "49") (name "Net-(IC1C-I1)") (class "Default")
      (node (ref "IC1") (pin "9") (pinfunction "I1_9") (pintype "input"))
      (node (ref "R27") (pin "1") (pinfunction "1_1") (pintype "passive"))
      (node (ref "S3") (pin "2") (pinfunction "2_2") (pintype "passive"))
    )
    (net (code "50") (name "Net-(IC1C-O)") (class "Default")
      (node (ref "IC1") (pin "10") (pinfunction "O_10") (pintype "output"))
      (node (ref "IC1") (pin "11") (pinfunction "I0_11") (pintype "input"))
      (node (ref "IC1") (pin "12") (pinfunction "I1_12") (pintype "input"))
    )
    (net (code "51") (name "Net-(IC1D-O)") (class "Default")
      (node (ref "IC1") (pin "13") (pinfunction "O_13") (pintype "output"))
      (node (ref "IC2") (pin "5") (pinfunction "I0_5") (pintype "input"))
    )
    (net (code "52") (name "Net-(IC2A-O)") (class "Default")
      (node (ref "IC2") (pin "1") (pinfunction "O_1") (pintype "output"))
      (node (ref "IC2") (pin "6") (pinfunction "I1_6") (pintype "input"))
    )
    (net (code "53") (name "Net-(IC2C-O)") (class "Default")
      (node (ref "IC2") (pin "10") (pinfunction "O_10") (pintype "output"))
      (node (ref "R3") (pin "1") (pinfunction "1_1") (pintype "passive"))
    )
    (net (code "54") (name "Net-(IC3A-I1)") (class "Default")
      (node (ref "C74") (pin "1") (pinfunction "1_1") (pintype "passive"))
      (node (ref "IC3") (pin "2") (pinfunction "I1_2") (pintype "input"))
      (node (ref "R3") (pin "2") (pinfunction "2_2") (pintype "passive"))
    )
    (net (code "55") (name "Net-(Q1-D)") (class "Default")
      (node (ref "C6") (pin "2") (pinfunction "2_2") (pintype "passive"))
      (node (ref "Q1") (pin "3") (pinfunction "D_3") (pintype "passive"))
      (node (ref "S2") (pin "1") (pinfunction "O_1") (pintype "passive"))
      (node (ref "TP4056X") (pin "5") (pinfunction "BAT_5") (pintype "bidirectional"))
      (node (ref "VBAT") (pin "1") (pinfunction "P_1") (pintype "passive"))
    )
    (net (code "56") (name "Net-(Q2-G)") (class "Default")
      (node (ref "Q2") (pin "1") (pinfunction "G_1") (pintype "passive"))
      (node (ref "S2") (pin "2") (pinfunction "P_2") (pintype "passive"))
    )
    (net (code "57") (name "Net-(R20-Pad1)") (class "Default")
      (node (ref "R20") (pin "1") (pinfunction "1_1") (pintype "passive"))
      (node (ref "T1") (pin "B") (pinfunction "B_B") (pintype "passive"))
    )
    (net (code "58") (name "Net-(R21-Pad1)") (class "Default")
      (node (ref "R21") (pin "1") (pinfunction "1_1") (pintype "passive"))
      (node (ref "T2") (pin "B") (pinfunction "B_B") (pintype "passive"))
    )
    (net (code "59") (name "Net-(RGB1-DO)") (class "Default")
      (node (ref "RGB1") (pin "2") (pinfunction "DO_2") (pintype "bidirectional"))
      (node (ref "RGB2") (pin "4") (pinfunction "DI_4") (pintype "bidirectional"))
    )
    (net (code "60") (name "Net-(RGB2-DO)") (class "Default")
      (node (ref "RGB2") (pin "2") (pinfunction "DO_2") (pintype "bidirectional"))
      (node (ref "RGB3") (pin "4") (pinfunction "DI_4") (pintype "bidirectional"))
    )
    (net (code "61") (name "Net-(RGB3-DO)") (class "Default")
      (node (ref "RGB3") (pin "2") (pinfunction "DO_2") (pintype "bidirectional"))
      (node (ref "RGB4") (pin "4") (pinfunction "DI_4") (pintype "bidirectional"))
    )
    (net (code "62") (name "Net-(RGB4-DO)") (class "Default")
      (node (ref "RGB4") (pin "2") (pinfunction "DO_2") (pintype "bidirectional"))
      (node (ref "RGB5") (pin "4") (pinfunction "DI_4") (pintype "bidirectional"))
    )
    (net (code "63") (name "Net-(RGB5-DO)") (class "Default")
      (node (ref "RGB5") (pin "2") (pinfunction "DO_2") (pintype "bidirectional"))
      (node (ref "RGB6") (pin "4") (pinfunction "DI_4") (pintype "bidirectional"))
    )
    (net (code "64") (name "Net-(RGB6-DO)") (class "Default")
      (node (ref "RGB6") (pin "2") (pinfunction "DO_2") (pintype "bidirectional"))
      (node (ref "RGB7") (pin "4") (pinfunction "DI_4") (pintype "bidirectional"))
    )
    (net (code "65") (name "Net-(RGB7-DO)") (class "Default")
      (node (ref "RGB7") (pin "2") (pinfunction "DO_2") (pintype "bidirectional"))
      (node (ref "RGB8") (pin "4") (pinfunction "DI_4") (pintype "bidirectional"))
    )
    (net (code "66") (name "Net-(RGB8-DO)") (class "Default")
      (node (ref "RGB8") (pin "2") (pinfunction "DO_2") (pintype "bidirectional"))
      (node (ref "RGB9") (pin "4") (pinfunction "DI_4") (pintype "bidirectional"))
    )
    (net (code "67") (name "Net-(RGB10-DI)") (class "Default")
      (node (ref "RGB10") (pin "4") (pinfunction "DI_4") (pintype "bidirectional"))
      (node (ref "RGB9") (pin "2") (pinfunction "DO_2") (pintype "bidirectional"))
    )
    (net (code "68") (name "Net-(RGB10-DO)") (class "Default")
      (node (ref "RGB10") (pin "2") (pinfunction "DO_2") (pintype "bidirectional"))
      (node (ref "RGB11") (pin "4") (pinfunction "DI_4") (pintype "bidirectional"))
    )
    (net (code "69") (name "Net-(RGB11-DO)") (class "Default")
      (node (ref "RGB11") (pin "2") (pinfunction "DO_2") (pintype "bidirectional"))
      (node (ref "RGB12") (pin "4") (pinfunction "DI_4") (pintype "bidirectional"))
    )
    (net (code "70") (name "Net-(RGB12-DO)") (class "Default")
      (node (ref "RGB12") (pin "2") (pinfunction "DO_2") (pintype "bidirectional"))
      (node (ref "RGB13") (pin "4") (pinfunction "DI_4") (pintype "bidirectional"))
    )
    (net (code "71") (name "Net-(RGB13-DO)") (class "Default")
      (node (ref "RGB13") (pin "2") (pinfunction "DO_2") (pintype "bidirectional"))
      (node (ref "RGB14") (pin "4") (pinfunction "DI_4") (pintype "bidirectional"))
    )
    (net (code "72") (name "Net-(RGB14-DO)") (class "Default")
      (node (ref "RGB14") (pin "2") (pinfunction "DO_2") (pintype "bidirectional"))
      (node (ref "RGB15") (pin "4") (pinfunction "DI_4") (pintype "bidirectional"))
    )
    (net (code "73") (name "Net-(RGB15-DO)") (class "Default")
      (node (ref "RGB15") (pin "2") (pinfunction "DO_2") (pintype "bidirectional"))
      (node (ref "RGB16") (pin "4") (pinfunction "DI_4") (pintype "bidirectional"))
    )
    (net (code "74") (name "Net-(RGB17-DO)") (class "Default")
      (node (ref "RGB17") (pin "2") (pinfunction "DO_2") (pintype "bidirectional"))
      (node (ref "RGB18") (pin "4") (pinfunction "DI_4") (pintype "bidirectional"))
    )
    (net (code "75") (name "Net-(RGB18-DO)") (class "Default")
      (node (ref "RGB18") (pin "2") (pinfunction "DO_2") (pintype "bidirectional"))
      (node (ref "RGB19") (pin "4") (pinfunction "DI_4") (pintype "bidirectional"))
    )
    (net (code "76") (name "Net-(RGB19-DO)") (class "Default")
      (node (ref "RGB19") (pin "2") (pinfunction "DO_2") (pintype "bidirectional"))
      (node (ref "RGB20") (pin "4") (pinfunction "DI_4") (pintype "bidirectional"))
    )
    (net (code "77") (name "Net-(RGB20-DO)") (class "Default")
      (node (ref "RGB20") (pin "2") (pinfunction "DO_2") (pintype "bidirectional"))
      (node (ref "RGB21") (pin "4") (pinfunction "DI_4") (pintype "bidirectional"))
    )
    (net (code "78") (name "Net-(RGB21-DO)") (class "Default")
      (node (ref "RGB21") (pin "2") (pinfunction "DO_2") (pintype "bidirectional"))
      (node (ref "RGB22") (pin "4") (pinfunction "DI_4") (pintype "bidirectional"))
    )
    (net (code "79") (name "Net-(RGB22-DO)") (class "Default")
      (node (ref "RGB22") (pin "2") (pinfunction "DO_2") (pintype "bidirectional"))
      (node (ref "RGB23") (pin "4") (pinfunction "DI_4") (pintype "bidirectional"))
    )
    (net (code "80") (name "Net-(RGB23-DO)") (class "Default")
      (node (ref "RGB23") (pin "2") (pinfunction "DO_2") (pintype "bidirectional"))
      (node (ref "RGB24") (pin "4") (pinfunction "DI_4") (pintype "bidirectional"))
    )
    (net (code "81") (name "Net-(RGB24-DO)") (class "Default")
      (node (ref "RGB24") (pin "2") (pinfunction "DO_2") (pintype "bidirectional"))
      (node (ref "RGB25") (pin "4") (pinfunction "DI_4") (pintype "bidirectional"))
    )
    (net (code "82") (name "Net-(RGB25-DO)") (class "Default")
      (node (ref "RGB25") (pin "2") (pinfunction "DO_2") (pintype "bidirectional"))
      (node (ref "RGB26") (pin "4") (pinfunction "DI_4") (pintype "bidirectional"))
    )
    (net (code "83") (name "Net-(RGB26-DO)") (class "Default")
      (node (ref "RGB26") (pin "2") (pinfunction "DO_2") (pintype "bidirectional"))
      (node (ref "RGB27") (pin "4") (pinfunction "DI_4") (pintype "bidirectional"))
    )
    (net (code "84") (name "Net-(RGB27-DO)") (class "Default")
      (node (ref "RGB27") (pin "2") (pinfunction "DO_2") (pintype "bidirectional"))
      (node (ref "RGB28") (pin "4") (pinfunction "DI_4") (pintype "bidirectional"))
    )
    (net (code "85") (name "Net-(RGB28-DO)") (class "Default")
      (node (ref "RGB28") (pin "2") (pinfunction "DO_2") (pintype "bidirectional"))
      (node (ref "RGB29") (pin "4") (pinfunction "DI_4") (pintype "bidirectional"))
    )
    (net (code "86") (name "Net-(RGB29-DO)") (class "Default")
      (node (ref "RGB29") (pin "2") (pinfunction "DO_2") (pintype "bidirectional"))
      (node (ref "RGB30") (pin "4") (pinfunction "DI_4") (pintype "bidirectional"))
    )
    (net (code "87") (name "Net-(RGB30-DO)") (class "Default")
      (node (ref "RGB30") (pin "2") (pinfunction "DO_2") (pintype "bidirectional"))
      (node (ref "RGB31") (pin "4") (pinfunction "DI_4") (pintype "bidirectional"))
    )
    (net (code "88") (name "Net-(RGB31-DO)") (class "Default")
      (node (ref "RGB31") (pin "2") (pinfunction "DO_2") (pintype "bidirectional"))
      (node (ref "RGB32") (pin "4") (pinfunction "DI_4") (pintype "bidirectional"))
    )
    (net (code "89") (name "Net-(RGB33-DO)") (class "Default")
      (node (ref "RGB33") (pin "2") (pinfunction "DO_2") (pintype "bidirectional"))
      (node (ref "RGB34") (pin "4") (pinfunction "DI_4") (pintype "bidirectional"))
    )
    (net (code "90") (name "Net-(RGB34-DO)") (class "Default")
      (node (ref "RGB34") (pin "2") (pinfunction "DO_2") (pintype "bidirectional"))
      (node (ref "RGB35") (pin "4") (pinfunction "DI_4") (pintype "bidirectional"))
    )
    (net (code "91") (name "Net-(RGB35-DO)") (class "Default")
      (node (ref "RGB35") (pin "2") (pinfunction "DO_2") (pintype "bidirectional"))
      (node (ref "RGB36") (pin "4") (pinfunction "DI_4") (pintype "bidirectional"))
    )
    (net (code "92") (name "Net-(RGB36-DO)") (class "Default")
      (node (ref "RGB36") (pin "2") (pinfunction "DO_2") (pintype "bidirectional"))
      (node (ref "RGB37") (pin "4") (pinfunction "DI_4") (pintype "bidirectional"))
    )
    (net (code "93") (name "Net-(RGB37-DO)") (class "Default")
      (node (ref "RGB37") (pin "2") (pinfunction "DO_2") (pintype "bidirectional"))
      (node (ref "RGB38") (pin "4") (pinfunction "DI_4") (pintype "bidirectional"))
    )
    (net (code "94") (name "Net-(RGB38-DO)") (class "Default")
      (node (ref "RGB38") (pin "2") (pinfunction "DO_2") (pintype "bidirectional"))
      (node (ref "RGB39") (pin "4") (pinfunction "DI_4") (pintype "bidirectional"))
    )
    (net (code "95") (name "Net-(RGB39-DO)") (class "Default")
      (node (ref "RGB39") (pin "2") (pinfunction "DO_2") (pintype "bidirectional"))
      (node (ref "RGB40") (pin "4") (pinfunction "DI_4") (pintype "bidirectional"))
    )
    (net (code "96") (name "Net-(RGB40-DO)") (class "Default")
      (node (ref "RGB40") (pin "2") (pinfunction "DO_2") (pintype "bidirectional"))
      (node (ref "RGB41") (pin "4") (pinfunction "DI_4") (pintype "bidirectional"))
    )
    (net (code "97") (name "Net-(RGB41-DO)") (class "Default")
      (node (ref "RGB41") (pin "2") (pinfunction "DO_2") (pintype "bidirectional"))
      (node (ref "RGB42") (pin "4") (pinfunction "DI_4") (pintype "bidirectional"))
    )
    (net (code "98") (name "Net-(RGB42-DO)") (class "Default")
      (node (ref "RGB42") (pin "2") (pinfunction "DO_2") (pintype "bidirectional"))
      (node (ref "RGB43") (pin "4") (pinfunction "DI_4") (pintype "bidirectional"))
    )
    (net (code "99") (name "Net-(RGB43-DO)") (class "Default")
      (node (ref "RGB43") (pin "2") (pinfunction "DO_2") (pintype "bidirectional"))
      (node (ref "RGB44") (pin "4") (pinfunction "DI_4") (pintype "bidirectional"))
    )
    (net (code "100") (name "Net-(RGB44-DO)") (class "Default")
      (node (ref "RGB44") (pin "2") (pinfunction "DO_2") (pintype "bidirectional"))
      (node (ref "RGB45") (pin "4") (pinfunction "DI_4") (pintype "bidirectional"))
    )
    (net (code "101") (name "Net-(RGB45-DO)") (class "Default")
      (node (ref "RGB45") (pin "2") (pinfunction "DO_2") (pintype "bidirectional"))
      (node (ref "RGB46") (pin "4") (pinfunction "DI_4") (pintype "bidirectional"))
    )
    (net (code "102") (name "Net-(RGB46-DO)") (class "Default")
      (node (ref "RGB46") (pin "2") (pinfunction "DO_2") (pintype "bidirectional"))
      (node (ref "RGB47") (pin "4") (pinfunction "DI_4") (pintype "bidirectional"))
    )
    (net (code "103") (name "Net-(RGB47-DO)") (class "Default")
      (node (ref "RGB47") (pin "2") (pinfunction "DO_2") (pintype "bidirectional"))
      (node (ref "RGB48") (pin "4") (pinfunction "DI_4") (pintype "bidirectional"))
    )
    (net (code "104") (name "Net-(RGB49-DO)") (class "Default")
      (node (ref "RGB49") (pin "2") (pinfunction "DO_2") (pintype "bidirectional"))
      (node (ref "RGB50") (pin "4") (pinfunction "DI_4") (pintype "bidirectional"))
    )
    (net (code "105") (name "Net-(RGB50-DO)") (class "Default")
      (node (ref "RGB50") (pin "2") (pinfunction "DO_2") (pintype "bidirectional"))
      (node (ref "RGB51") (pin "4") (pinfunction "DI_4") (pintype "bidirectional"))
    )
    (net (code "106") (name "Net-(RGB51-DO)") (class "Default")
      (node (ref "RGB51") (pin "2") (pinfunction "DO_2") (pintype "bidirectional"))
      (node (ref "RGB52") (pin "4") (pinfunction "DI_4") (pintype "bidirectional"))
    )
    (net (code "107") (name "Net-(RGB52-DO)") (class "Default")
      (node (ref "RGB52") (pin "2") (pinfunction "DO_2") (pintype "bidirectional"))
      (node (ref "RGB53") (pin "4") (pinfunction "DI_4") (pintype "bidirectional"))
    )
    (net (code "108") (name "Net-(RGB53-DO)") (class "Default")
      (node (ref "RGB53") (pin "2") (pinfunction "DO_2") (pintype "bidirectional"))
      (node (ref "RGB54") (pin "4") (pinfunction "DI_4") (pintype "bidirectional"))
    )
    (net (code "109") (name "Net-(RGB54-DO)") (class "Default")
      (node (ref "RGB54") (pin "2") (pinfunction "DO_2") (pintype "bidirectional"))
      (node (ref "RGB55") (pin "4") (pinfunction "DI_4") (pintype "bidirectional"))
    )
    (net (code "110") (name "Net-(RGB55-DO)") (class "Default")
      (node (ref "RGB55") (pin "2") (pinfunction "DO_2") (pintype "bidirectional"))
      (node (ref "RGB56") (pin "4") (pinfunction "DI_4") (pintype "bidirectional"))
    )
    (net (code "111") (name "Net-(RGB56-DO)") (class "Default")
      (node (ref "RGB56") (pin "2") (pinfunction "DO_2") (pintype "bidirectional"))
      (node (ref "RGB57") (pin "4") (pinfunction "DI_4") (pintype "bidirectional"))
    )
    (net (code "112") (name "Net-(RGB57-DO)") (class "Default")
      (node (ref "RGB57") (pin "2") (pinfunction "DO_2") (pintype "bidirectional"))
      (node (ref "RGB58") (pin "4") (pinfunction "DI_4") (pintype "bidirectional"))
    )
    (net (code "113") (name "Net-(RGB58-DO)") (class "Default")
      (node (ref "RGB58") (pin "2") (pinfunction "DO_2") (pintype "bidirectional"))
      (node (ref "RGB59") (pin "4") (pinfunction "DI_4") (pintype "bidirectional"))
    )
    (net (code "114") (name "Net-(RGB59-DO)") (class "Default")
      (node (ref "RGB59") (pin "2") (pinfunction "DO_2") (pintype "bidirectional"))
      (node (ref "RGB60") (pin "4") (pinfunction "DI_4") (pintype "bidirectional"))
    )
    (net (code "115") (name "Net-(RGB60-DO)") (class "Default")
      (node (ref "RGB60") (pin "2") (pinfunction "DO_2") (pintype "bidirectional"))
      (node (ref "RGB61") (pin "4") (pinfunction "DI_4") (pintype "bidirectional"))
    )
    (net (code "116") (name "Net-(RGB61-DO)") (class "Default")
      (node (ref "RGB61") (pin "2") (pinfunction "DO_2") (pintype "bidirectional"))
      (node (ref "RGB62") (pin "4") (pinfunction "DI_4") (pintype "bidirectional"))
    )
    (net (code "117") (name "Net-(RGB62-DO)") (class "Default")
      (node (ref "RGB62") (pin "2") (pinfunction "DO_2") (pintype "bidirectional"))
      (node (ref "RGB63") (pin "4") (pinfunction "DI_4") (pintype "bidirectional"))
    )
    (net (code "118") (name "Net-(RGB63-DO)") (class "Default")
      (node (ref "RGB63") (pin "2") (pinfunction "DO_2") (pintype "bidirectional"))
      (node (ref "RGB64") (pin "4") (pinfunction "DI_4") (pintype "bidirectional"))
    )
    (net (code "119") (name "Net-(TP4056X-CHRG)") (class "Default")
      (node (ref "D2") (pin "C") (pinfunction "C_C") (pintype "passive"))
      (node (ref "TP4056X") (pin "7") (pinfunction "CHRG_7") (pintype "bidirectional"))
    )
    (net (code "120") (name "Net-(TP4056X-PROG)") (class "Default")
      (node (ref "R15") (pin "2") (pinfunction "2_2") (pintype "passive"))
      (node (ref "TP4056X") (pin "2") (pinfunction "PROG_2") (pintype "bidirectional"))
    )
    (net (code "121") (name "Net-(TP4056X-STDBY)") (class "Default")
      (node (ref "D3") (pin "C") (pinfunction "C_C") (pintype "passive"))
      (node (ref "TP4056X") (pin "6") (pinfunction "STDBY_6") (pintype "bidirectional"))
    )
    (net (code "122") (name "Net-(USB-C-CC1)") (class "Default")
      (node (ref "R22") (pin "2") (pinfunction "2_2") (pintype "passive"))
      (node (ref "USB-C") (pin "4") (pinfunction "CC1_4") (pintype "bidirectional"))
    )
    (net (code "123") (name "Net-(USB-C-CC2)") (class "Default")
      (node (ref "R13") (pin "2") (pinfunction "2_2") (pintype "passive"))
      (node (ref "USB-C") (pin "10") (pinfunction "CC2_10") (pintype "bidirectional"))
    )
    (net (code "124") (name "VBAT") (class "Default")
      (node (ref "C7") (pin "1") (pinfunction "1_1") (pintype "passive"))
      (node (ref "C8") (pin "1") (pinfunction "1_1") (pintype "passive"))
      (node (ref "CH340C") (pin "16") (pinfunction "VCC_16") (pintype "bidirectional"))
    )
    (net (code "125") (name "VBAT-1") (class "Default")
      (node (ref "C41") (pin "2") (pinfunction "2_2") (pintype "passive"))
      (node (ref "C42") (pin "2") (pinfunction "2_2") (pintype "passive"))
      (node (ref "C43") (pin "2") (pinfunction "2_2") (pintype "passive"))
      (node (ref "C44") (pin "2") (pinfunction "2_2") (pintype "passive"))
      (node (ref "C45") (pin "2") (pinfunction "2_2") (pintype "passive"))
      (node (ref "C46") (pin "2") (pinfunction "2_2") (pintype "passive"))
      (node (ref "C47") (pin "2") (pinfunction "2_2") (pintype "passive"))
      (node (ref "C48") (pin "2") (pinfunction "2_2") (pintype "passive"))
      (node (ref "C49") (pin "2") (pinfunction "2_2") (pintype "passive"))
      (node (ref "C50") (pin "2") (pinfunction "2_2") (pintype "passive"))
      (node (ref "C51") (pin "2") (pinfunction "2_2") (pintype "passive"))
      (node (ref "C52") (pin "2") (pinfunction "2_2") (pintype "passive"))
      (node (ref "C53") (pin "2") (pinfunction "2_2") (pintype "passive"))
      (node (ref "C54") (pin "2") (pinfunction "2_2") (pintype "passive"))
      (node (ref "C55") (pin "2") (pinfunction "2_2") (pintype "passive"))
      (node (ref "C56") (pin "2") (pinfunction "2_2") (pintype "passive"))
      (node (ref "RGB33") (pin "1") (pinfunction "VDD_1") (pintype "bidirectional"))
      (node (ref "RGB34") (pin "1") (pinfunction "VDD_1") (pintype "bidirectional"))
      (node (ref "RGB35") (pin "1") (pinfunction "VDD_1") (pintype "bidirectional"))
      (node (ref "RGB36") (pin "1") (pinfunction "VDD_1") (pintype "bidirectional"))
      (node (ref "RGB37") (pin "1") (pinfunction "VDD_1") (pintype "bidirectional"))
      (node (ref "RGB38") (pin "1") (pinfunction "VDD_1") (pintype "bidirectional"))
      (node (ref "RGB39") (pin "1") (pinfunction "VDD_1") (pintype "bidirectional"))
      (node (ref "RGB40") (pin "1") (pinfunction "VDD_1") (pintype "bidirectional"))
      (node (ref "RGB41") (pin "1") (pinfunction "VDD_1") (pintype "bidirectional"))
      (node (ref "RGB42") (pin "1") (pinfunction "VDD_1") (pintype "bidirectional"))
      (node (ref "RGB43") (pin "1") (pinfunction "VDD_1") (pintype "bidirectional"))
      (node (ref "RGB44") (pin "1") (pinfunction "VDD_1") (pintype "bidirectional"))
      (node (ref "RGB45") (pin "1") (pinfunction "VDD_1") (pintype "bidirectional"))
      (node (ref "RGB46") (pin "1") (pinfunction "VDD_1") (pintype "bidirectional"))
      (node (ref "RGB47") (pin "1") (pinfunction "VDD_1") (pintype "bidirectional"))
      (node (ref "RGB48") (pin "1") (pinfunction "VDD_1") (pintype "bidirectional"))
      (node (ref "VCC-USB-1") (pin "1") (pinfunction "P_1") (pintype "passive"))
    )
    (net (code "126") (name "VBAT-2") (class "Default")
      (node (ref "C2") (pin "1") (pinfunction "1_1") (pintype "passive"))
      (node (ref "C57") (pin "2") (pinfunction "2_2") (pintype "passive"))
      (node (ref "C58") (pin "2") (pinfunction "2_2") (pintype "passive"))
      (node (ref "C59") (pin "2") (pinfunction "2_2") (pintype "passive"))
      (node (ref "C60") (pin "2") (pinfunction "2_2") (pintype "passive"))
      (node (ref "C61") (pin "2") (pinfunction "2_2") (pintype "passive"))
      (node (ref "C62") (pin "2") (pinfunction "2_2") (pintype "passive"))
      (node (ref "C63") (pin "2") (pinfunction "2_2") (pintype "passive"))
      (node (ref "C64") (pin "2") (pinfunction "2_2") (pintype "passive"))
      (node (ref "C65") (pin "2") (pinfunction "2_2") (pintype "passive"))
      (node (ref "C66") (pin "2") (pinfunction "2_2") (pintype "passive"))
      (node (ref "C67") (pin "2") (pinfunction "2_2") (pintype "passive"))
      (node (ref "C68") (pin "2") (pinfunction "2_2") (pintype "passive"))
      (node (ref "C69") (pin "2") (pinfunction "2_2") (pintype "passive"))
      (node (ref "C70") (pin "2") (pinfunction "2_2") (pintype "passive"))
      (node (ref "C71") (pin "2") (pinfunction "2_2") (pintype "passive"))
      (node (ref "C72") (pin "2") (pinfunction "2_2") (pintype "passive"))
      (node (ref "D1") (pin "C") (pinfunction "C_C") (pintype "passive"))
      (node (ref "NCP114") (pin "1") (pinfunction "IN_1") (pintype "bidirectional"))
      (node (ref "NCP114") (pin "3") (pinfunction "EN_3") (pintype "bidirectional"))
      (node (ref "Q1") (pin "2") (pinfunction "S_2") (pintype "passive"))
      (node (ref "RGB49") (pin "1") (pinfunction "VDD_1") (pintype "bidirectional"))
      (node (ref "RGB50") (pin "1") (pinfunction "VDD_1") (pintype "bidirectional"))
      (node (ref "RGB51") (pin "1") (pinfunction "VDD_1") (pintype "bidirectional"))
      (node (ref "RGB52") (pin "1") (pinfunction "VDD_1") (pintype "bidirectional"))
      (node (ref "RGB53") (pin "1") (pinfunction "VDD_1") (pintype "bidirectional"))
      (node (ref "RGB54") (pin "1") (pinfunction "VDD_1") (pintype "bidirectional"))
      (node (ref "RGB55") (pin "1") (pinfunction "VDD_1") (pintype "bidirectional"))
      (node (ref "RGB56") (pin "1") (pinfunction "VDD_1") (pintype "bidirectional"))
      (node (ref "RGB57") (pin "1") (pinfunction "VDD_1") (pintype "bidirectional"))
      (node (ref "RGB58") (pin "1") (pinfunction "VDD_1") (pintype "bidirectional"))
      (node (ref "RGB59") (pin "1") (pinfunction "VDD_1") (pintype "bidirectional"))
      (node (ref "RGB60") (pin "1") (pinfunction "VDD_1") (pintype "bidirectional"))
      (node (ref "RGB61") (pin "1") (pinfunction "VDD_1") (pintype "bidirectional"))
      (node (ref "RGB62") (pin "1") (pinfunction "VDD_1") (pintype "bidirectional"))
      (node (ref "RGB63") (pin "1") (pinfunction "VDD_1") (pintype "bidirectional"))
      (node (ref "RGB64") (pin "1") (pinfunction "VDD_1") (pintype "bidirectional"))
      (node (ref "VCC2") (pin "1") (pinfunction "P_1") (pintype "passive"))
      (node (ref "VCC3") (pin "1") (pinfunction "P_1") (pintype "passive"))
    )
    (net (code "127") (name "VBAT-3") (class "Default")
      (node (ref "C10") (pin "2") (pinfunction "2_2") (pintype "passive"))
      (node (ref "C11") (pin "2") (pinfunction "2_2") (pintype "passive"))
      (node (ref "C12") (pin "2") (pinfunction "2_2") (pintype "passive"))
      (node (ref "C13") (pin "2") (pinfunction "2_2") (pintype "passive"))
      (node (ref "C14") (pin "2") (pinfunction "2_2") (pintype "passive"))
      (node (ref "C15") (pin "2") (pinfunction "2_2") (pintype "passive"))
      (node (ref "C16") (pin "2") (pinfunction "2_2") (pintype "passive"))
      (node (ref "C17") (pin "2") (pinfunction "2_2") (pintype "passive"))
      (node (ref "C18") (pin "2") (pinfunction "2_2") (pintype "passive"))
      (node (ref "C19") (pin "2") (pinfunction "2_2") (pintype "passive"))
      (node (ref "C20") (pin "2") (pinfunction "2_2") (pintype "passive"))
      (node (ref "C21") (pin "2") (pinfunction "2_2") (pintype "passive"))
      (node (ref "C22") (pin "2") (pinfunction "2_2") (pintype "passive"))
      (node (ref "C23") (pin "2") (pinfunction "2_2") (pintype "passive"))
      (node (ref "C24") (pin "2") (pinfunction "2_2") (pintype "passive"))
      (node (ref "C9") (pin "2") (pinfunction "2_2") (pintype "passive"))
      (node (ref "R14") (pin "2") (pinfunction "2_2") (pintype "passive"))
      (node (ref "RGB1") (pin "1") (pinfunction "VDD_1") (pintype "bidirectional"))
      (node (ref "RGB10") (pin "1") (pinfunction "VDD_1") (pintype "bidirectional"))
      (node (ref "RGB11") (pin "1") (pinfunction "VDD_1") (pintype "bidirectional"))
      (node (ref "RGB12") (pin "1") (pinfunction "VDD_1") (pintype "bidirectional"))
      (node (ref "RGB13") (pin "1") (pinfunction "VDD_1") (pintype "bidirectional"))
      (node (ref "RGB14") (pin "1") (pinfunction "VDD_1") (pintype "bidirectional"))
      (node (ref "RGB15") (pin "1") (pinfunction "VDD_1") (pintype "bidirectional"))
      (node (ref "RGB16") (pin "1") (pinfunction "VDD_1") (pintype "bidirectional"))
      (node (ref "RGB2") (pin "1") (pinfunction "VDD_1") (pintype "bidirectional"))
      (node (ref "RGB3") (pin "1") (pinfunction "VDD_1") (pintype "bidirectional"))
      (node (ref "RGB4") (pin "1") (pinfunction "VDD_1") (pintype "bidirectional"))
      (node (ref "RGB5") (pin "1") (pinfunction "VDD_1") (pintype "bidirectional"))
      (node (ref "RGB6") (pin "1") (pinfunction "VDD_1") (pintype "bidirectional"))
      (node (ref "RGB7") (pin "1") (pinfunction "VDD_1") (pintype "bidirectional"))
      (node (ref "RGB8") (pin "1") (pinfunction "VDD_1") (pintype "bidirectional"))
      (node (ref "RGB9") (pin "1") (pinfunction "VDD_1") (pintype "bidirectional"))
      (node (ref "VCC1") (pin "1") (pinfunction "P_1") (pintype "passive"))
      (node (ref "VCC4") (pin "1") (pinfunction "P_1") (pintype "passive"))
      (node (ref "VCC5") (pin "1") (pinfunction "P_1") (pintype "passive"))
      (node (ref "VCC6") (pin "1") (pinfunction "P_1") (pintype "passive"))
    )
    (net (code "128") (name "VBAT-4") (class "Default")
      (node (ref "C25") (pin "2") (pinfunction "2_2") (pintype "passive"))
      (node (ref "C26") (pin "2") (pinfunction "2_2") (pintype "passive"))
      (node (ref "C27") (pin "2") (pinfunction "2_2") (pintype "passive"))
      (node (ref "C28") (pin "2") (pinfunction "2_2") (pintype "passive"))
      (node (ref "C29") (pin "2") (pinfunction "2_2") (pintype "passive"))
      (node (ref "C30") (pin "2") (pinfunction "2_2") (pintype "passive"))
      (node (ref "C31") (pin "2") (pinfunction "2_2") (pintype "passive"))
      (node (ref "C32") (pin "2") (pinfunction "2_2") (pintype "passive"))
      (node (ref "C33") (pin "2") (pinfunction "2_2") (pintype "passive"))
      (node (ref "C34") (pin "2") (pinfunction "2_2") (pintype "passive"))
      (node (ref "C35") (pin "2") (pinfunction "2_2") (pintype "passive"))
      (node (ref "C36") (pin "2") (pinfunction "2_2") (pintype "passive"))
      (node (ref "C37") (pin "2") (pinfunction "2_2") (pintype "passive"))
      (node (ref "C38") (pin "2") (pinfunction "2_2") (pintype "passive"))
      (node (ref "C39") (pin "2") (pinfunction "2_2") (pintype "passive"))
      (node (ref "C40") (pin "2") (pinfunction "2_2") (pintype "passive"))
      (node (ref "RGB17") (pin "1") (pinfunction "VDD_1") (pintype "bidirectional"))
      (node (ref "RGB18") (pin "1") (pinfunction "VDD_1") (pintype "bidirectional"))
      (node (ref "RGB19") (pin "1") (pinfunction "VDD_1") (pintype "bidirectional"))
      (node (ref "RGB20") (pin "1") (pinfunction "VDD_1") (pintype "bidirectional"))
      (node (ref "RGB21") (pin "1") (pinfunction "VDD_1") (pintype "bidirectional"))
      (node (ref "RGB22") (pin "1") (pinfunction "VDD_1") (pintype "bidirectional"))
      (node (ref "RGB23") (pin "1") (pinfunction "VDD_1") (pintype "bidirectional"))
      (node (ref "RGB24") (pin "1") (pinfunction "VDD_1") (pintype "bidirectional"))
      (node (ref "RGB25") (pin "1") (pinfunction "VDD_1") (pintype "bidirectional"))
      (node (ref "RGB26") (pin "1") (pinfunction "VDD_1") (pintype "bidirectional"))
      (node (ref "RGB27") (pin "1") (pinfunction "VDD_1") (pintype "bidirectional"))
      (node (ref "RGB28") (pin "1") (pinfunction "VDD_1") (pintype "bidirectional"))
      (node (ref "RGB29") (pin "1") (pinfunction "VDD_1") (pintype "bidirectional"))
      (node (ref "RGB30") (pin "1") (pinfunction "VDD_1") (pintype "bidirectional"))
      (node (ref "RGB31") (pin "1") (pinfunction "VDD_1") (pintype "bidirectional"))
      (node (ref "RGB32") (pin "1") (pinfunction "VDD_1") (pintype "bidirectional"))
      (node (ref "VCC-USB-3") (pin "1") (pinfunction "P_1") (pintype "passive"))
    )
    (net (code "129") (name "VCC-2") (class "Default")
      (node (ref "C3") (pin "1") (pinfunction "1_1") (pintype "passive"))
      (node (ref "IC1") (pin "14") (pinfunction "VCC_14") (pintype "power_in"))
      (node (ref "IC2") (pin "14") (pinfunction "VCC_14") (pintype "power_in"))
      (node (ref "IC3") (pin "5") (pinfunction "VCC_5") (pintype "power_in"))
      (node (ref "NCP114") (pin "5") (pinfunction "OUT_5") (pintype "bidirectional"))
      (node (ref "R24") (pin "1") (pinfunction "1_1") (pintype "passive"))
      (node (ref "S3") (pin "1") (pinfunction "1_1") (pintype "passive"))
      (node (ref "VCC-USB-11") (pin "1") (pinfunction "P_1") (pintype "passive"))
    )
    (net (code "130") (name "VCC-3") (class "Default")
      (node (ref "ADXL345") (pin "1") (pinfunction "VDD_1") (pintype "bidirectional"))
      (node (ref "ADXL345") (pin "6") (pinfunction "VS_6") (pintype "bidirectional"))
      (node (ref "C1") (pin "1") (pinfunction "1_1") (pintype "passive"))
      (node (ref "C4") (pin "1") (pinfunction "1_1") (pintype "passive"))
      (node (ref "R2") (pin "1") (pinfunction "1_1") (pintype "passive"))
      (node (ref "R4") (pin "1") (pinfunction "1_1") (pintype "passive"))
      (node (ref "R5") (pin "1") (pinfunction "1_1") (pintype "passive"))
      (node (ref "R6") (pin "2") (pinfunction "2_2") (pintype "passive"))
      (node (ref "R8") (pin "2") (pinfunction "2_2") (pintype "passive"))
      (node (ref "R9") (pin "2") (pinfunction "2_2") (pintype "passive"))
      (node (ref "U1") (pin "VCC") (pinfunction "VCC_VCC") (pintype "bidirectional"))
      (node (ref "VCC-USB-21") (pin "1") (pinfunction "P_1") (pintype "passive"))
    )
    (net (code "131") (name "VCC-USB-1") (class "Default")
      (node (ref "USB-C") (pin "11") (pinfunction "VBUS_11") (pintype "bidirectional"))
      (node (ref "USB-C") (pin "2") (pinfunction "VBUS_2") (pintype "bidirectional"))
      (node (ref "VCC-USB-14") (pin "1") (pinfunction "P_1") (pintype "passive"))
    )
    (net (code "132") (name "VCC-USB-2") (class "Default")
      (node (ref "C5") (pin "2") (pinfunction "2_2") (pintype "passive"))
      (node (ref "D1") (pin "A") (pinfunction "A_A") (pintype "passive"))
      (node (ref "Q1") (pin "1") (pinfunction "G_1") (pintype "passive"))
      (node (ref "R11") (pin "2") (pinfunction "2_2") (pintype "passive"))
      (node (ref "R16") (pin "2") (pinfunction "2_2") (pintype "passive"))
      (node (ref "R17") (pin "2") (pinfunction "2_2") (pintype "passive"))
      (node (ref "TP4056X") (pin "4") (pinfunction "VCC_4") (pintype "bidirectional"))
      (node (ref "TP4056X") (pin "8") (pinfunction "CE_8") (pintype "bidirectional"))
      (node (ref "VCC-USB-20") (pin "1") (pinfunction "P_1") (pintype "passive"))
    )
    (net (code "133") (name "unconnected-(ADXL345-INT2-Pad9)") (class "Default")
      (node (ref "ADXL345") (pin "9") (pinfunction "INT2_9") (pintype "bidirectional"))
    )
    (net (code "134") (name "unconnected-(ADXL345-NC-Pad3)") (class "Default")
      (node (ref "ADXL345") (pin "3") (pinfunction "NC_3") (pintype "bidirectional"))
    )
    (net (code "135") (name "unconnected-(ADXL345-NC-Pad10)") (class "Default")
      (node (ref "ADXL345") (pin "10") (pinfunction "NC_10") (pintype "bidirectional"))
    )
    (net (code "136") (name "unconnected-(ADXL345-NC-Pad11)") (class "Default")
      (node (ref "ADXL345") (pin "11") (pinfunction "NC_11") (pintype "bidirectional"))
    )
    (net (code "137") (name "unconnected-(CH340C-CTS-Pad9)") (class "Default")
      (node (ref "CH340C") (pin "9") (pinfunction "CTS_9") (pintype "bidirectional"))
    )
    (net (code "138") (name "unconnected-(CH340C-DCD-Pad12)") (class "Default")
      (node (ref "CH340C") (pin "12") (pinfunction "DCD_12") (pintype "bidirectional"))
    )
    (net (code "139") (name "unconnected-(CH340C-DSR-Pad10)") (class "Default")
      (node (ref "CH340C") (pin "10") (pinfunction "DSR_10") (pintype "bidirectional"))
    )
    (net (code "140") (name "unconnected-(CH340C-RI-Pad11)") (class "Default")
      (node (ref "CH340C") (pin "11") (pinfunction "RI_11") (pintype "bidirectional"))
    )
    (net (code "141") (name "unconnected-(CH340C-RS232-Pad15)") (class "Default")
      (node (ref "CH340C") (pin "15") (pinfunction "RS232_15") (pintype "bidirectional"))
    )
    (net (code "142") (name "unconnected-(CH340C-XI-Pad7)") (class "Default")
      (node (ref "CH340C") (pin "7") (pinfunction "XI_7") (pintype "bidirectional"))
    )
    (net (code "143") (name "unconnected-(CH340C-XO-Pad8)") (class "Default")
      (node (ref "CH340C") (pin "8") (pinfunction "XO_8") (pintype "bidirectional"))
    )
    (net (code "144") (name "unconnected-(RGB32-DO-Pad2)") (class "Default")
      (node (ref "RGB32") (pin "2") (pinfunction "DO_2") (pintype "bidirectional"))
    )
    (net (code "145") (name "unconnected-(U1-*GPIO9-PadGPIO9)") (class "Default")
      (node (ref "U1") (pin "GPIO9") (pinfunction "*GPIO9_GPIO9") (pintype "bidirectional"))
    )
    (net (code "146") (name "unconnected-(U1-*GPIO10-PadGPIO10)") (class "Default")
      (node (ref "U1") (pin "GPIO10") (pinfunction "*GPIO10_GPIO10") (pintype "bidirectional"))
    )
    (net (code "147") (name "unconnected-(U1-PadCS0)") (class "Default")
      (node (ref "U1") (pin "CS0") (pinfunction "CS0_CS0") (pintype "bidirectional"))
    )
    (net (code "148") (name "unconnected-(U1-PadMISO)") (class "Default")
      (node (ref "U1") (pin "MISO") (pinfunction "MISO_MISO") (pintype "bidirectional"))
    )
    (net (code "149") (name "unconnected-(U1-PadMOSI)") (class "Default")
      (node (ref "U1") (pin "MOSI") (pinfunction "MOSI_MOSI") (pintype "bidirectional"))
    )
    (net (code "150") (name "unconnected-(U1-PadSCLK)") (class "Default")
      (node (ref "U1") (pin "SCLK") (pinfunction "SCLK_SCLK") (pintype "bidirectional"))
    )
    (net (code "151") (name "unconnected-(USB-C-SBU1-Pad9)") (class "Default")
      (node (ref "USB-C") (pin "9") (pinfunction "SBU1_9") (pintype "bidirectional"))
    )
    (net (code "152") (name "unconnected-(USB-C-SBU2-Pad3)") (class "Default")
      (node (ref "USB-C") (pin "3") (pinfunction "SBU2_3") (pintype "bidirectional"))
    )
  )
)
